# DynoHub.net
KiCad netlist of a schematic drawn in EAGLE
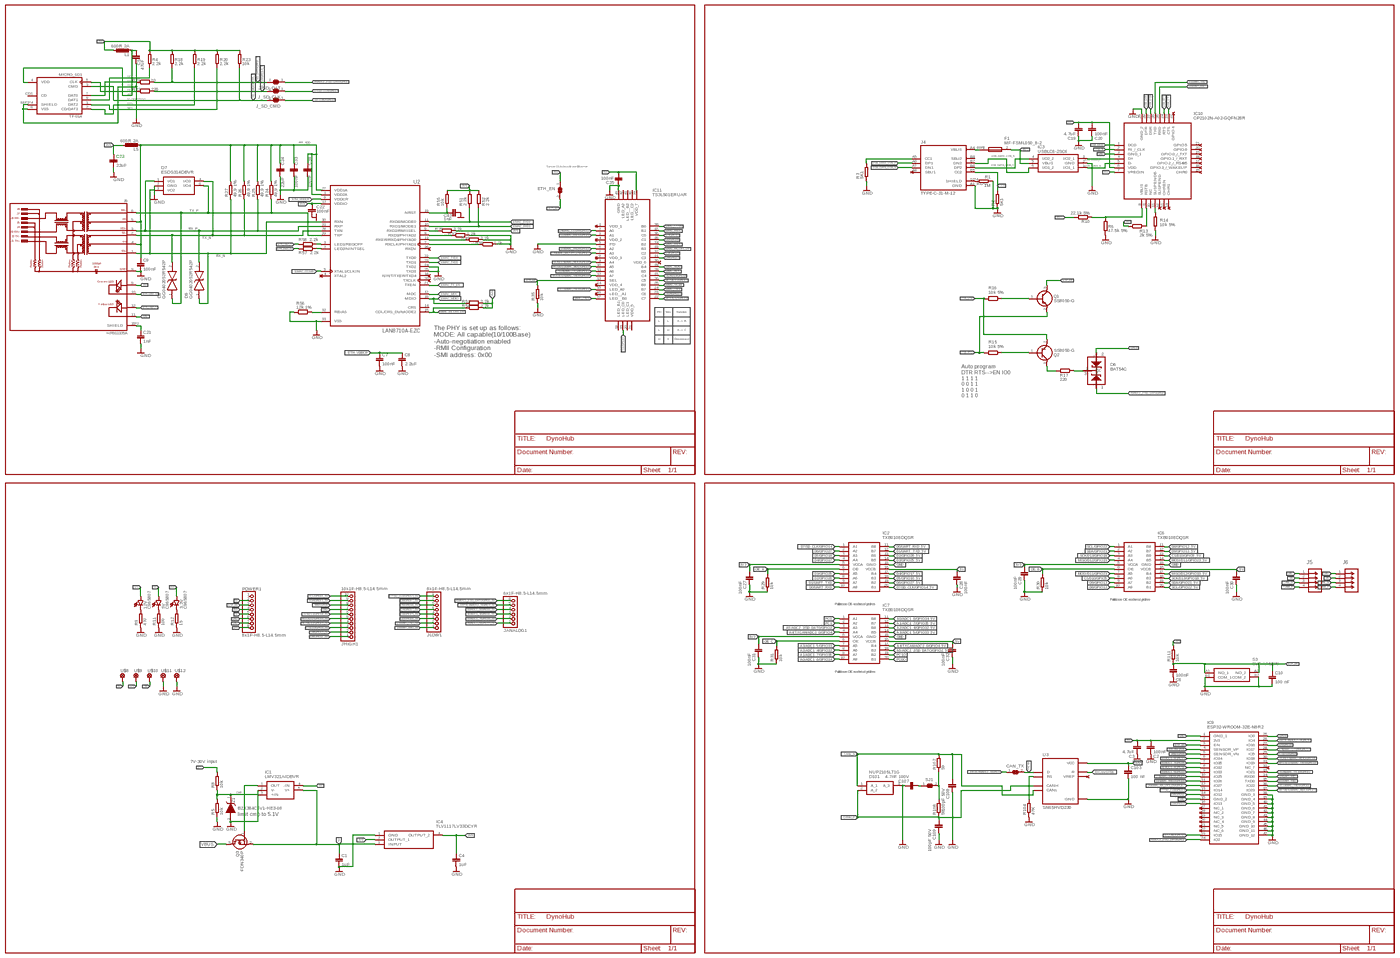
[diagram p0: schematic, sheet 1, overview]
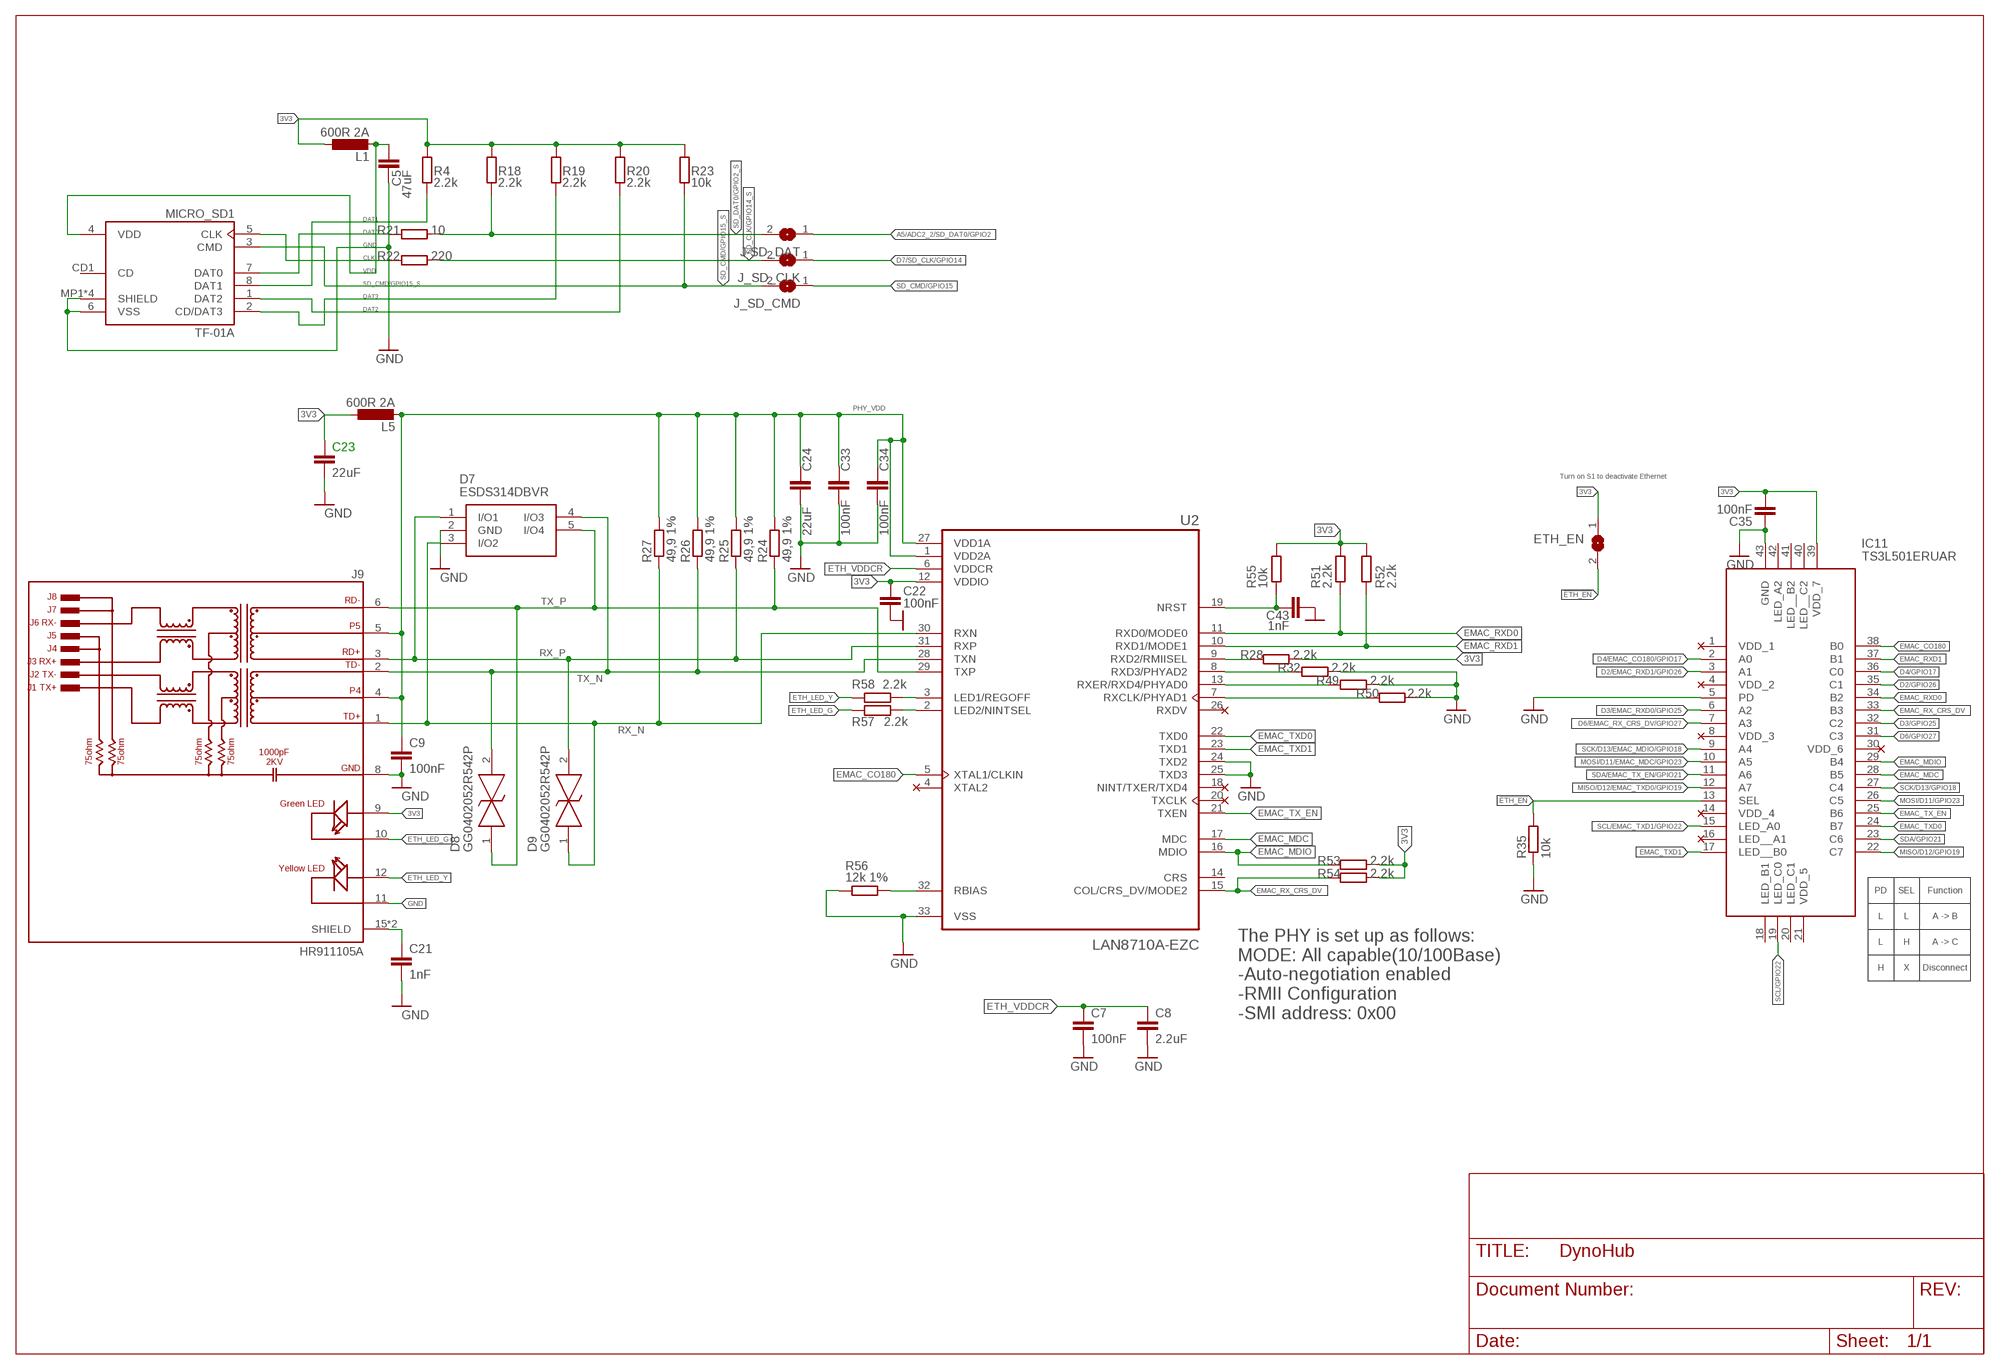
[diagram p1: schematic, sheet 1, part 1 of 4]
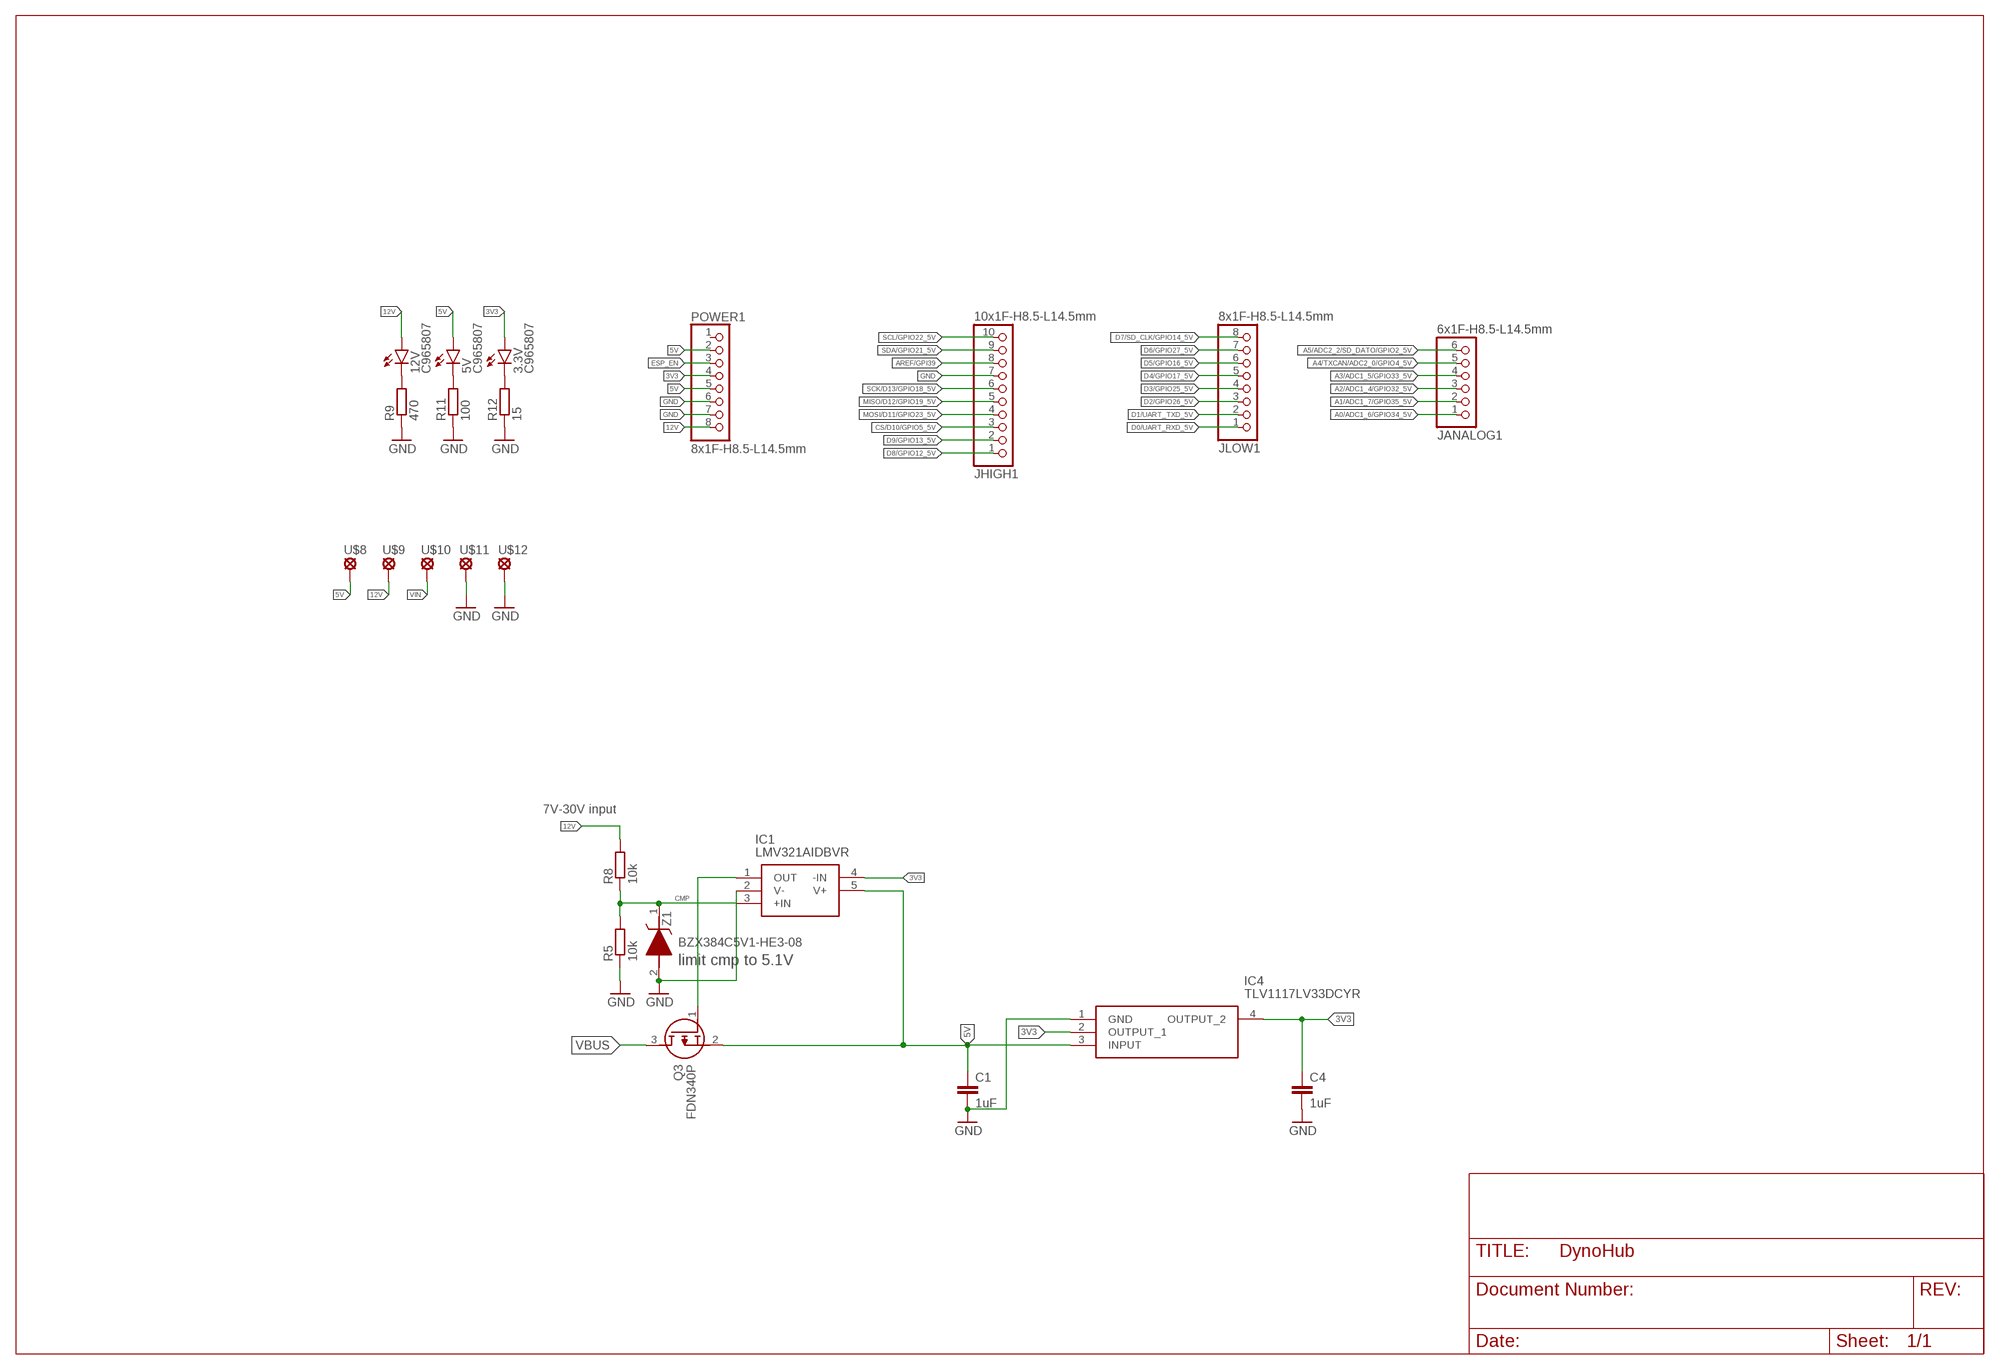
[diagram p2: schematic, sheet 1, part 2 of 4]
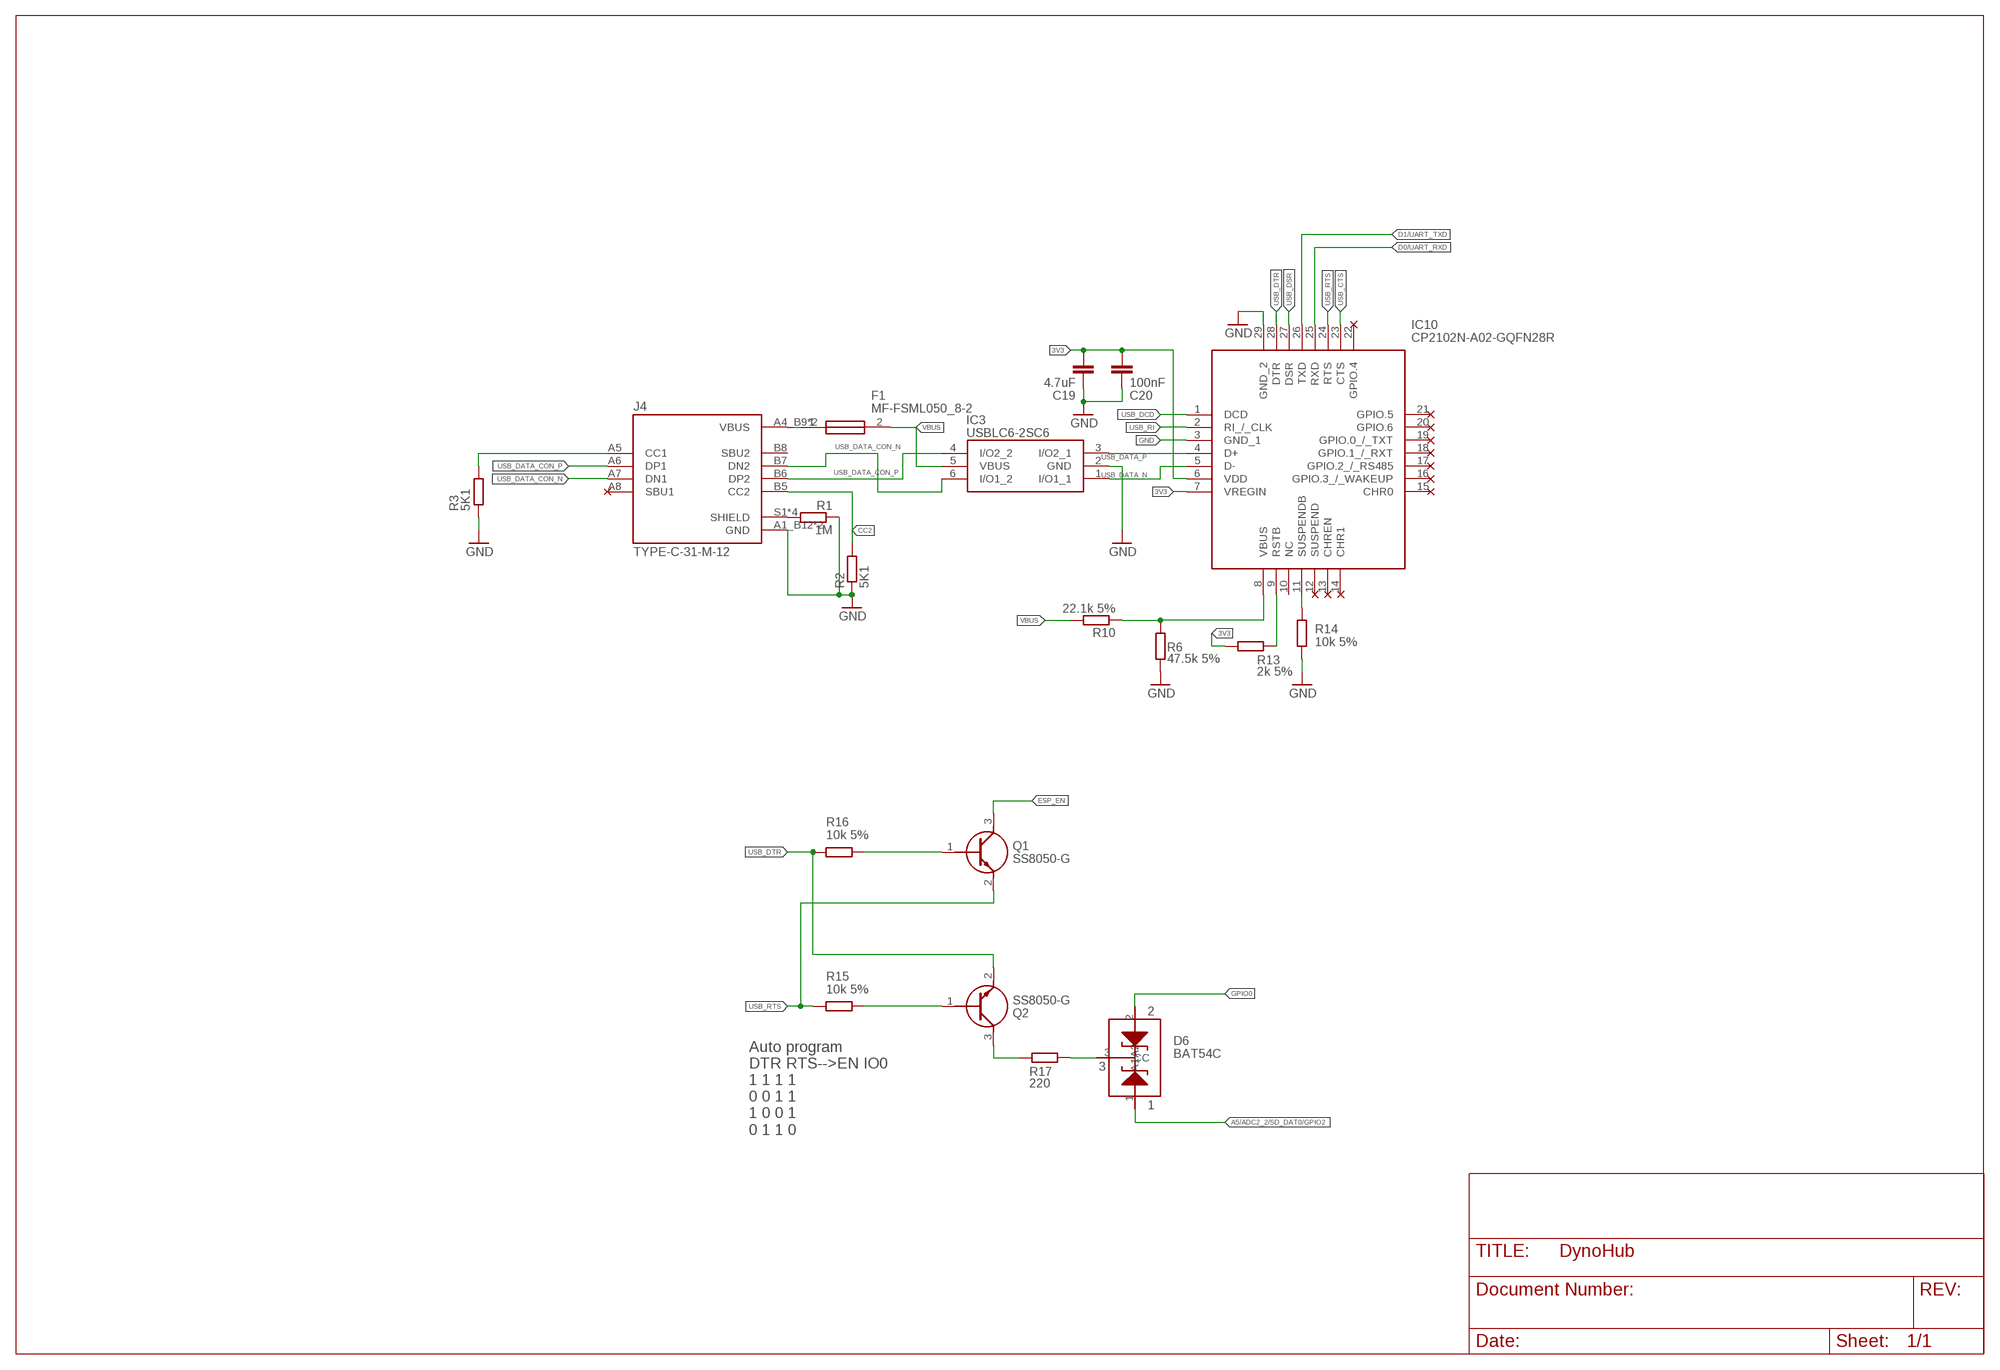
[diagram p3: schematic, sheet 1, part 3 of 4]
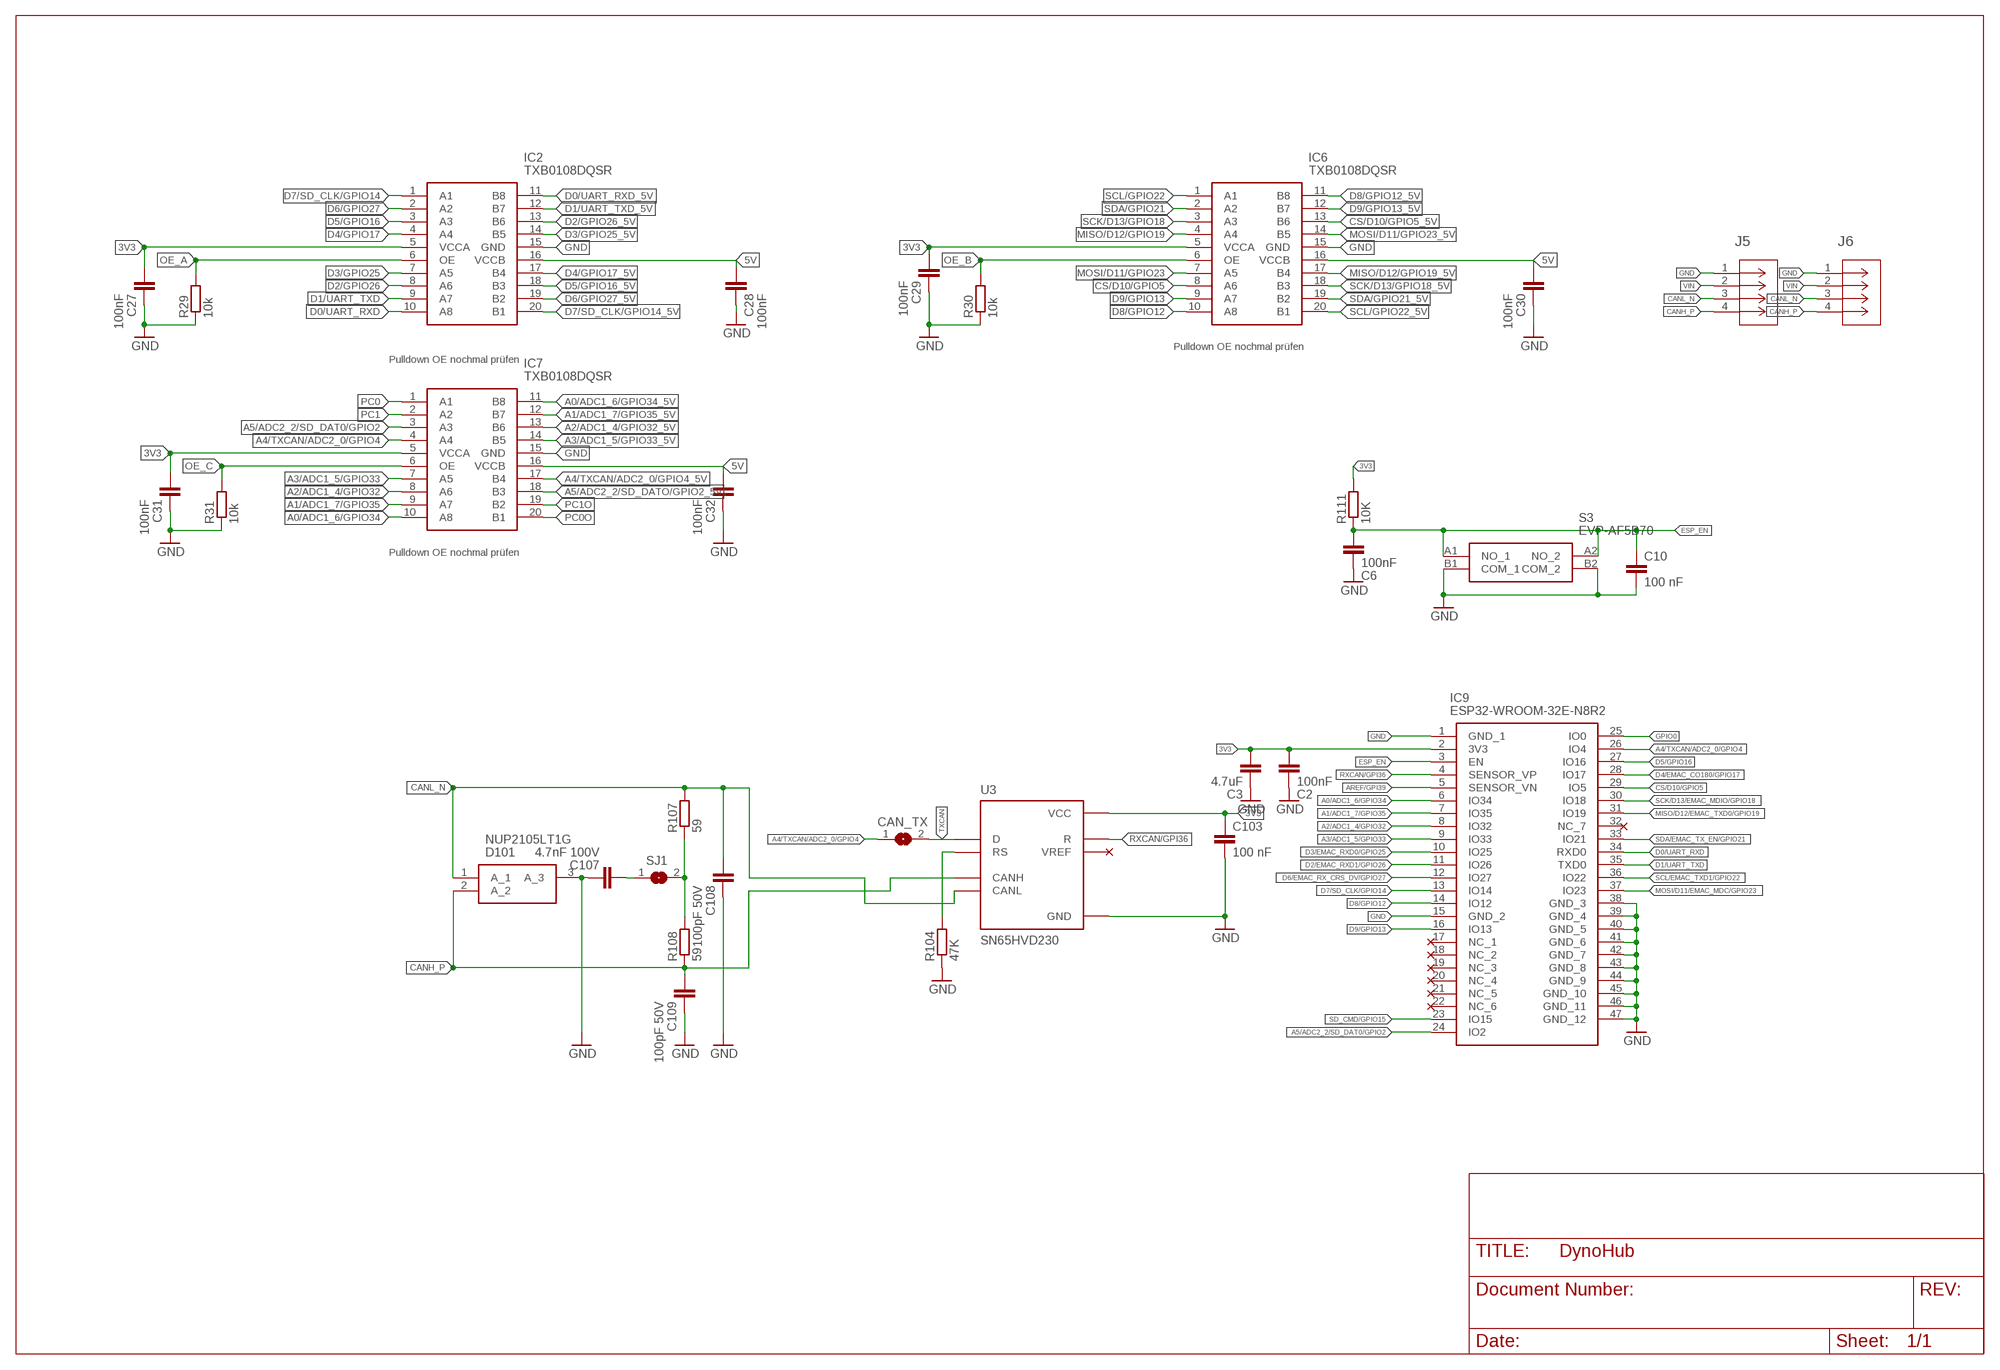
[diagram p4: schematic, sheet 1, part 4 of 4]

(export (version "E")
  (design (tool "Eeschema 10.0.6"))
  (components
    (comp (ref "3.3V")
      (value "C965807")
      (footprint "eagle-import:CHIPLED_0603")
      (libsource (lib "eagle-import") (part "LEDCHIPLED_0603"))
    )
    (comp (ref "5V")
      (value "C965807")
      (footprint "eagle-import:CHIPLED_0603")
      (libsource (lib "eagle-import") (part "LEDCHIPLED_0603"))
    )
    (comp (ref "12V")
      (value "C965807")
      (footprint "eagle-import:CHIPLED_0603")
      (libsource (lib "eagle-import") (part "LEDCHIPLED_0603"))
    )
    (comp (ref "C1")
      (value "1uF")
      (footprint "eagle-import:C0603")
      (libsource (lib "eagle-import") (part "C-EUC0603"))
    )
    (comp (ref "C2")
      (value "100nF")
      (footprint "eagle-import:C0402K")
      (libsource (lib "eagle-import") (part "C-EUC0402K"))
    )
    (comp (ref "C3")
      (value "4.7uF")
      (footprint "eagle-import:C0402K")
      (libsource (lib "eagle-import") (part "C-EUC0402K"))
    )
    (comp (ref "C4")
      (value "1uF")
      (footprint "eagle-import:C0603")
      (libsource (lib "eagle-import") (part "C-EUC0603"))
    )
    (comp (ref "C5")
      (value "47uF")
      (footprint "eagle-import:C0805")
      (libsource (lib "eagle-import") (part "C-EUC0805"))
    )
    (comp (ref "C6")
      (value "100nF")
      (footprint "eagle-import:C0402K")
      (libsource (lib "eagle-import") (part "C-EUC0402K"))
    )
    (comp (ref "C7")
      (value "100nF")
      (footprint "eagle-import:C0402K")
      (libsource (lib "eagle-import") (part "C-EUC0402K"))
    )
    (comp (ref "C8")
      (value "2.2uF")
      (footprint "eagle-import:C0402K")
      (libsource (lib "eagle-import") (part "C-EUC0402K"))
    )
    (comp (ref "C9")
      (value "100nF")
      (footprint "eagle-import:C0402K")
      (libsource (lib "eagle-import") (part "C-EUC0402K"))
    )
    (comp (ref "C10")
      (value "100 nF")
      (footprint "eagle-import:C0402K")
      (libsource (lib "eagle-import") (part "resistor_348_C-EUC0402K"))
    )
    (comp (ref "C19")
      (value "4.7uF")
      (footprint "eagle-import:C0603")
      (libsource (lib "eagle-import") (part "C-EUC0603"))
    )
    (comp (ref "C20")
      (value "100nF")
      (footprint "eagle-import:C0402K")
      (libsource (lib "eagle-import") (part "C-EUC0402K"))
    )
    (comp (ref "C21")
      (value "1nF")
      (footprint "eagle-import:C0402K")
      (libsource (lib "eagle-import") (part "C-EUC0402K"))
    )
    (comp (ref "C22")
      (value "100nF")
      (footprint "eagle-import:C0402K")
      (libsource (lib "eagle-import") (part "C-EUC0402K"))
    )
    (comp (ref "C23")
      (value "22uF")
      (footprint "eagle-import:C0603")
      (libsource (lib "eagle-import") (part "C-EUC0603"))
    )
    (comp (ref "C24")
      (value "22uF")
      (footprint "eagle-import:C0603")
      (libsource (lib "eagle-import") (part "C-EUC0603"))
    )
    (comp (ref "C27")
      (value "100nF")
      (footprint "eagle-import:C0603")
      (libsource (lib "eagle-import") (part "resistor_348_C-EUC0603"))
    )
    (comp (ref "C28")
      (value "100nF")
      (footprint "eagle-import:C0603")
      (libsource (lib "eagle-import") (part "resistor_348_C-EUC0603"))
    )
    (comp (ref "C29")
      (value "100nF")
      (footprint "eagle-import:C0402K")
      (libsource (lib "eagle-import") (part "resistor_348_C-EUC0402K"))
    )
    (comp (ref "C30")
      (value "100nF")
      (footprint "eagle-import:C0402K")
      (libsource (lib "eagle-import") (part "resistor_348_C-EUC0402K"))
    )
    (comp (ref "C31")
      (value "100nF")
      (footprint "eagle-import:C0603")
      (libsource (lib "eagle-import") (part "resistor_348_C-EUC0603"))
    )
    (comp (ref "C32")
      (value "100nF")
      (footprint "eagle-import:C0603")
      (libsource (lib "eagle-import") (part "resistor_348_C-EUC0603"))
    )
    (comp (ref "C33")
      (value "100nF")
      (footprint "eagle-import:C0402K")
      (libsource (lib "eagle-import") (part "C-EUC0402K"))
    )
    (comp (ref "C34")
      (value "100nF")
      (footprint "eagle-import:C0402K")
      (libsource (lib "eagle-import") (part "C-EUC0402K"))
    )
    (comp (ref "C35")
      (value "100nF")
      (footprint "eagle-import:C0402K")
      (libsource (lib "eagle-import") (part "C-EUC0402K"))
    )
    (comp (ref "C43")
      (value "1nF")
      (footprint "eagle-import:C0402K")
      (libsource (lib "eagle-import") (part "C-EUC0402K"))
    )
    (comp (ref "C103")
      (value "100 nF")
      (footprint "eagle-import:C0402K")
      (libsource (lib "eagle-import") (part "resistor_348_C-EUC0402K"))
    )
    (comp (ref "C107")
      (value "4.7nF 100V")
      (footprint "eagle-import:C0603")
      (libsource (lib "eagle-import") (part "resistor_348_C-EUC0603"))
    )
    (comp (ref "C108")
      (value "100pF 50V")
      (footprint "eagle-import:C0603")
      (libsource (lib "eagle-import") (part "resistor_348_C-EUC0603"))
    )
    (comp (ref "C109")
      (value "100pF 50V")
      (footprint "eagle-import:C0603")
      (libsource (lib "eagle-import") (part "resistor_348_C-EUC0603"))
    )
    (comp (ref "CAN_TX")
      (value "SJ")
      (footprint "eagle-import:SJ")
      (libsource (lib "eagle-import") (part "jumper_45683683_SJ"))
    )
    (comp (ref "D6")
      (value "BAT54C")
      (footprint "eagle-import:SOT95P240X120-3N")
      (fields (field (name "MOUSER_PART_NUMBER") "583-BAT54C"))
      (libsource (lib "eagle-import") (part "BAT54C"))
    )
    (comp (ref "D7")
      (value "ESDS314DBVR")
      (footprint "eagle-import:SOT95P280X145-5N")
      (fields (field (name "MOUSER_PART_NUMBER") "595-ESDS314DBVR"))
      (libsource (lib "eagle-import") (part "ESDS314DBVR"))
    )
    (comp (ref "D8")
      (value "GG0402052R542P")
      (footprint "eagle-import:DIONC1006X55N")
      (fields (field (name "MOUSER_PART_NUMBER") "581-GG0402052R542P"))
      (libsource (lib "eagle-import") (part "GG0402052R542P"))
    )
    (comp (ref "D9")
      (value "GG0402052R542P")
      (footprint "eagle-import:DIONC1006X55N")
      (fields (field (name "MOUSER_PART_NUMBER") "581-GG0402052R542P"))
      (libsource (lib "eagle-import") (part "GG0402052R542P"))
    )
    (comp (ref "D101")
      (value "NUP2105LT1G")
      (footprint "eagle-import:SOT96P237X111-3N")
      (fields (field (name "MOUSER_PART_NUMBER") "863-NUP2105LT1G"))
      (libsource (lib "eagle-import") (part "NUP2105LT1G"))
    )
    (comp (ref "ETH_EN")
      (value "SJ")
      (footprint "eagle-import:SJ")
      (libsource (lib "eagle-import") (part "SJ"))
    )
    (comp (ref "F1")
      (value "MF-FSML050_8-2")
      (footprint "eagle-import:FUSC1608X70N")
      (fields
        (field (name "MANUFACTURER_PART_NUMBER") "MF-FSML050/8-2")
        (field (name "MOUSER_PART_NUMBER") "652-MF-FSML050/8-2")
      )
      (libsource (lib "eagle-import") (part "MF-FSML050_8-2"))
    )
    (comp (ref "IC1")
      (value "LMV321AIDBVR")
      (footprint "eagle-import:SOT95P280X145-5N")
      (fields (field (name "MOUSER_PART_NUMBER") "595-LMV321AIDBVR"))
      (libsource (lib "eagle-import") (part "LMV321AIDBVR"))
    )
    (comp (ref "IC2")
      (value "TXB0108DQSR")
      (footprint "eagle-import:TXB0108DQSR")
      (fields (field (name "MOUSER_PART_NUMBER") "595-TXB0108DQSR"))
      (libsource (lib "eagle-import") (part "TXB0108DQSR"))
    )
    (comp (ref "IC3")
      (value "USBLC6-2SC6")
      (footprint "eagle-import:SOT95P280X145-6N")
      (fields (field (name "MOUSER_PART_NUMBER") "511-USBLC6-2SC6"))
      (libsource (lib "eagle-import") (part "USBLC6-2SC6"))
    )
    (comp (ref "IC4")
      (value "TLV1117LV33DCYR")
      (footprint "eagle-import:SOT230P700X180-4N")
      (fields (field (name "MOUSER_PART_NUMBER") "595-TLV1117LV33DCYR"))
      (libsource (lib "eagle-import") (part "TLV1117LV33DCYR"))
    )
    (comp (ref "IC6")
      (value "TXB0108DQSR")
      (footprint "eagle-import:TXB0108DQSR")
      (fields (field (name "MOUSER_PART_NUMBER") "595-TXB0108DQSR"))
      (libsource (lib "eagle-import") (part "TXB0108DQSR"))
    )
    (comp (ref "IC7")
      (value "TXB0108DQSR")
      (footprint "eagle-import:TXB0108DQSR")
      (fields (field (name "MOUSER_PART_NUMBER") "595-TXB0108DQSR"))
      (libsource (lib "eagle-import") (part "TXB0108DQSR"))
    )
    (comp (ref "IC9")
      (value "ESP32-WROOM-32E-N8R2")
      (footprint "eagle-import:ESP32WROOM32EN8R2")
      (fields (field (name "MOUSER_PART_NUMBER") "356-ESP32WRM32EN8R2"))
      (libsource (lib "eagle-import") (part "ESP32-WROOM-32E-N8R2"))
    )
    (comp (ref "IC10")
      (value "CP2102N-A02-GQFN28R")
      (footprint "eagle-import:QFN50P500X500X80-29N")
      (fields (field (name "MOUSER_PART_NUMBER") "634-CP2102NA02QFN28R"))
      (libsource (lib "eagle-import") (part "CP2102N-A02-GQFN28R"))
    )
    (comp (ref "IC11")
      (value "TS3L501ERUAR")
      (footprint "eagle-import:QFN50P350X900X80-43N")
      (fields (field (name "MOUSER_PART_NUMBER") "595-TS3L501ERUAR"))
      (libsource (lib "eagle-import") (part "TS3L501ERUAR"))
    )
    (comp (ref "J-SD_DAT")
      (value "SJ")
      (footprint "eagle-import:SJ")
      (libsource (lib "eagle-import") (part "SJ"))
    )
    (comp (ref "J4")
      (value "TYPE-C-31-M-12")
      (footprint "eagle-import:HRO_TYPE-C-31-M-12")
      (fields (field (name "MF") "HRO Electronics Co., Ltd."))
      (libsource (lib "eagle-import") (part "TYPE-C-31-M-12"))
    )
    (comp (ref "J5")
      (value "1718570004CONN_SD-171857-0001_M265_04_MO")
      (footprint "eagle-import:CONN_SD-171857-0001_M265_04_MO")
      (fields
        (field (name "MANUFACTURER_PART_NUMBER") "1718570004")
        (field (name "COPYRIGHT") "Copyright (C) 2025 Ultra Librarian. All rights reserved.")
      )
      (libsource (lib "eagle-import") (part "1718570004CONN_SD-171857-0001_M265_04_MO"))
    )
    (comp (ref "J6")
      (value "1718570004CONN_SD-171857-0001_M265_04_MO")
      (footprint "eagle-import:CONN_SD-171857-0001_M265_04_MO")
      (fields
        (field (name "MANUFACTURER_PART_NUMBER") "1718570004")
        (field (name "COPYRIGHT") "Copyright (C) 2025 Ultra Librarian. All rights reserved.")
      )
      (libsource (lib "eagle-import") (part "1718570004CONN_SD-171857-0001_M265_04_MO"))
    )
    (comp (ref "J9")
      (value "HR911105A")
      (footprint "eagle-import:HANRUN_HR911105A")
      (fields (field (name "MF") "hanrun"))
      (libsource (lib "eagle-import") (part "HR911105A"))
    )
    (comp (ref "JANALOG1")
      (value "6x1F-H8.5-L14.5mm")
      (footprint "eagle-import:1X06")
      (libsource (lib "eagle-import") (part "PINHD-1X6"))
    )
    (comp (ref "JHIGH1")
      (value "10x1F-H8.5-L14.5mm")
      (footprint "eagle-import:1X10")
      (libsource (lib "eagle-import") (part "PINHD-1X10"))
    )
    (comp (ref "JLOW1")
      (value "8x1F-H8.5-L14.5mm")
      (footprint "eagle-import:1X08")
      (libsource (lib "eagle-import") (part "PINHD-1X8"))
    )
    (comp (ref "J_SD_CLK")
      (value "SJ")
      (footprint "eagle-import:SJ")
      (libsource (lib "eagle-import") (part "SJ"))
    )
    (comp (ref "J_SD_CMD")
      (value "SJ")
      (footprint "eagle-import:SJ")
      (libsource (lib "eagle-import") (part "SJ"))
    )
    (comp (ref "L1")
      (value "600R 2A")
      (footprint "eagle-import:L2012C")
      (libsource (lib "eagle-import") (part "L-EUL2012C"))
    )
    (comp (ref "L5")
      (value "600R 2A")
      (footprint "eagle-import:L2012C")
      (libsource (lib "eagle-import") (part "L-EUL2012C"))
    )
    (comp (ref "MICRO_SD1")
      (value "TF-01A")
      (footprint "eagle-import:TF-01A")
      (fields (field (name "MF") "HRO Electronics Co., Ltd."))
      (libsource (lib "eagle-import") (part "TF-01A"))
    )
    (comp (ref "POWER1")
      (value "8x1F-H8.5-L14.5mm")
      (footprint "eagle-import:1X08")
      (libsource (lib "eagle-import") (part "PINHD-1X8"))
    )
    (comp (ref "Q1")
      (value "SS8050-G")
      (footprint "eagle-import:SOT95P240X115-3N")
      (fields (field (name "MOUSER_PART_NUMBER") "750-SS8050-G"))
      (libsource (lib "eagle-import") (part "SS8050-G"))
    )
    (comp (ref "Q2")
      (value "SS8050-G")
      (footprint "eagle-import:SOT95P240X115-3N")
      (fields (field (name "MOUSER_PART_NUMBER") "750-SS8050-G"))
      (libsource (lib "eagle-import") (part "SS8050-G"))
    )
    (comp (ref "Q3")
      (value "FDN340P")
      (footprint "eagle-import:SOT95P237X112-3N")
      (fields (field (name "MOUSER_PART_NUMBER") "512-FDN340P"))
      (libsource (lib "eagle-import") (part "FDN340P"))
    )
    (comp (ref "R1")
      (value "1M")
      (footprint "eagle-import:R0603")
      (libsource (lib "eagle-import") (part "resistor_348_R-EU_R0603"))
    )
    (comp (ref "R2")
      (value "5K1")
      (footprint "eagle-import:R0603")
      (libsource (lib "eagle-import") (part "resistor_348_R-EU_R0603"))
    )
    (comp (ref "R3")
      (value "5K1")
      (footprint "eagle-import:R0603")
      (libsource (lib "eagle-import") (part "resistor_348_R-EU_R0603"))
    )
    (comp (ref "R4")
      (value "2.2k")
      (footprint "eagle-import:R0402")
      (libsource (lib "eagle-import") (part "R-EU_R0402"))
    )
    (comp (ref "R5")
      (value "10k")
      (footprint "eagle-import:R0603")
      (libsource (lib "eagle-import") (part "resistor_348_R-EU_R0603"))
    )
    (comp (ref "R6")
      (value "47.5k 5%")
      (footprint "eagle-import:R0402")
      (libsource (lib "eagle-import") (part "R-EU_R0402"))
    )
    (comp (ref "R8")
      (value "10k")
      (footprint "eagle-import:R0603")
      (libsource (lib "eagle-import") (part "resistor_348_R-EU_R0603"))
    )
    (comp (ref "R9")
      (value "470")
      (footprint "eagle-import:R0603")
      (libsource (lib "eagle-import") (part "resistor_348_R-EU_R0603"))
    )
    (comp (ref "R10")
      (value "22.1k 5%")
      (footprint "eagle-import:R0402")
      (libsource (lib "eagle-import") (part "R-EU_R0402"))
    )
    (comp (ref "R11")
      (value "100")
      (footprint "eagle-import:R0603")
      (libsource (lib "eagle-import") (part "resistor_348_R-EU_R0603"))
    )
    (comp (ref "R12")
      (value "15")
      (footprint "eagle-import:R0603")
      (libsource (lib "eagle-import") (part "resistor_348_R-EU_R0603"))
    )
    (comp (ref "R13")
      (value "2k 5%")
      (footprint "eagle-import:R0402")
      (libsource (lib "eagle-import") (part "R-EU_R0402"))
    )
    (comp (ref "R14")
      (value "10k 5%")
      (footprint "eagle-import:R0402")
      (libsource (lib "eagle-import") (part "R-EU_R0402"))
    )
    (comp (ref "R15")
      (value "10k 5%")
      (footprint "eagle-import:R0402")
      (libsource (lib "eagle-import") (part "R-EU_R0402"))
    )
    (comp (ref "R16")
      (value "10k 5%")
      (footprint "eagle-import:R0402")
      (libsource (lib "eagle-import") (part "R-EU_R0402"))
    )
    (comp (ref "R17")
      (value "220")
      (footprint "eagle-import:R0402")
      (libsource (lib "eagle-import") (part "R-EU_R0402"))
    )
    (comp (ref "R18")
      (value "2.2k")
      (footprint "eagle-import:R0402")
      (libsource (lib "eagle-import") (part "R-EU_R0402"))
    )
    (comp (ref "R19")
      (value "2.2k")
      (footprint "eagle-import:R0402")
      (libsource (lib "eagle-import") (part "R-EU_R0402"))
    )
    (comp (ref "R20")
      (value "2.2k")
      (footprint "eagle-import:R0402")
      (libsource (lib "eagle-import") (part "R-EU_R0402"))
    )
    (comp (ref "R21")
      (value "10")
      (footprint "eagle-import:R0402")
      (libsource (lib "eagle-import") (part "R-EU_R0402"))
    )
    (comp (ref "R22")
      (value "220")
      (footprint "eagle-import:R0402")
      (libsource (lib "eagle-import") (part "R-EU_R0402"))
    )
    (comp (ref "R23")
      (value "10k")
      (footprint "eagle-import:R0402")
      (libsource (lib "eagle-import") (part "R-EU_R0402"))
    )
    (comp (ref "R24")
      (value "49,9 1%")
      (footprint "eagle-import:R0402")
      (libsource (lib "eagle-import") (part "R-EU_R0402"))
    )
    (comp (ref "R25")
      (value "49,9 1%")
      (footprint "eagle-import:R0402")
      (libsource (lib "eagle-import") (part "R-EU_R0402"))
    )
    (comp (ref "R26")
      (value "49,9 1%")
      (footprint "eagle-import:R0402")
      (libsource (lib "eagle-import") (part "R-EU_R0402"))
    )
    (comp (ref "R27")
      (value "49,9 1%")
      (footprint "eagle-import:R0402")
      (libsource (lib "eagle-import") (part "R-EU_R0402"))
    )
    (comp (ref "R28")
      (value "2.2k")
      (footprint "eagle-import:R0402")
      (libsource (lib "eagle-import") (part "R-EU_R0402"))
    )
    (comp (ref "R29")
      (value "10k")
      (footprint "eagle-import:R0603")
      (libsource (lib "eagle-import") (part "resistor_348_R-EU_R0603"))
    )
    (comp (ref "R30")
      (value "10k")
      (footprint "eagle-import:R0402")
      (libsource (lib "eagle-import") (part "resistor_348_R-EU_R0402"))
    )
    (comp (ref "R31")
      (value "10k")
      (footprint "eagle-import:R0603")
      (libsource (lib "eagle-import") (part "resistor_348_R-EU_R0603"))
    )
    (comp (ref "R32")
      (value "2.2k")
      (footprint "eagle-import:R0402")
      (libsource (lib "eagle-import") (part "R-EU_R0402"))
    )
    (comp (ref "R35")
      (value "10k")
      (footprint "eagle-import:R0603")
      (libsource (lib "eagle-import") (part "resistor_348_R-EU_R0603"))
    )
    (comp (ref "R49")
      (value "2.2k")
      (footprint "eagle-import:R0402")
      (libsource (lib "eagle-import") (part "R-EU_R0402"))
    )
    (comp (ref "R50")
      (value "2.2k")
      (footprint "eagle-import:R0402")
      (libsource (lib "eagle-import") (part "R-EU_R0402"))
    )
    (comp (ref "R51")
      (value "2.2k")
      (footprint "eagle-import:R0402")
      (libsource (lib "eagle-import") (part "R-EU_R0402"))
    )
    (comp (ref "R52")
      (value "2.2k")
      (footprint "eagle-import:R0402")
      (libsource (lib "eagle-import") (part "R-EU_R0402"))
    )
    (comp (ref "R53")
      (value "2.2k")
      (footprint "eagle-import:R0603")
      (libsource (lib "eagle-import") (part "R-EU_R0603"))
    )
    (comp (ref "R54")
      (value "2.2k")
      (footprint "eagle-import:R0603")
      (libsource (lib "eagle-import") (part "R-EU_R0603"))
    )
    (comp (ref "R55")
      (value "10k")
      (footprint "eagle-import:R0402")
      (libsource (lib "eagle-import") (part "R-EU_R0402"))
    )
    (comp (ref "R56")
      (value "12k 1%")
      (footprint "eagle-import:R0402")
      (libsource (lib "eagle-import") (part "R-EU_R0402"))
    )
    (comp (ref "R57")
      (value "2.2k")
      (footprint "eagle-import:R0402")
      (libsource (lib "eagle-import") (part "R-EU_R0402"))
    )
    (comp (ref "R58")
      (value "2.2k")
      (footprint "eagle-import:R0402")
      (libsource (lib "eagle-import") (part "R-EU_R0402"))
    )
    (comp (ref "R104")
      (value "47K")
      (footprint "eagle-import:R0603")
      (libsource (lib "eagle-import") (part "resistor_348_R-EU_R0603"))
    )
    (comp (ref "R107")
      (value "59")
      (footprint "eagle-import:R0603")
      (libsource (lib "eagle-import") (part "resistor_348_R-EU_R0603"))
    )
    (comp (ref "R108")
      (value "59")
      (footprint "eagle-import:R0603")
      (libsource (lib "eagle-import") (part "resistor_348_R-EU_R0603"))
    )
    (comp (ref "R111")
      (value "10K")
      (footprint "eagle-import:R0402")
      (libsource (lib "eagle-import") (part "R-EU_R0402"))
    )
    (comp (ref "S3")
      (value "EVP-AF5B70")
      (footprint "eagle-import:EVPAF5B70")
      (fields (field (name "MOUSER_PART_NUMBER") "667-EVP-AF5B70"))
      (libsource (lib "eagle-import") (part "EVP-AF5B70"))
    )
    (comp (ref "SJ1")
      (value "SJ")
      (footprint "eagle-import:SJ")
      (libsource (lib "eagle-import") (part "jumper_45683683_SJ"))
    )
    (comp (ref "U$1") (value "NC") (footprint "eagle-import:NC") (libsource (lib "eagle-import") (part "NC")))
    (comp (ref "U$2") (value "NC") (footprint "eagle-import:NC") (libsource (lib "eagle-import") (part "NC")))
    (comp (ref "U$3") (value "NC") (footprint "eagle-import:NC") (libsource (lib "eagle-import") (part "NC")))
    (comp (ref "U$4") (value "NC") (footprint "eagle-import:NC") (libsource (lib "eagle-import") (part "NC")))
    (comp (ref "U$5") (value "NC") (footprint "eagle-import:NC") (libsource (lib "eagle-import") (part "NC")))
    (comp (ref "U$6") (value "NC") (footprint "eagle-import:NC") (libsource (lib "eagle-import") (part "NC")))
    (comp (ref "U$7") (value "NC") (footprint "eagle-import:NC") (libsource (lib "eagle-import") (part "NC")))
    (comp (ref "U$8")
      (value "2X3MM_PAD")
      (footprint "eagle-import:2X3MM_PAD")
      (libsource (lib "eagle-import") (part "2X3MM_PAD"))
    )
    (comp (ref "U$9")
      (value "2X3MM_PAD")
      (footprint "eagle-import:2X3MM_PAD")
      (libsource (lib "eagle-import") (part "2X3MM_PAD"))
    )
    (comp (ref "U$10")
      (value "2X3MM_PAD")
      (footprint "eagle-import:2X3MM_PAD")
      (libsource (lib "eagle-import") (part "2X3MM_PAD"))
    )
    (comp (ref "U$11")
      (value "2X3MM_PAD")
      (footprint "eagle-import:2X3MM_PAD")
      (libsource (lib "eagle-import") (part "2X3MM_PAD"))
    )
    (comp (ref "U$12")
      (value "2X3MM_PAD")
      (footprint "eagle-import:2X3MM_PAD")
      (libsource (lib "eagle-import") (part "2X3MM_PAD"))
    )
    (comp (ref "U$13")
      (value "NC")
      (footprint "eagle-import:NC")
      (libsource (lib "eagle-import") (part "NC"))
    )
    (comp (ref "U$14")
      (value "NC")
      (footprint "eagle-import:NC")
      (libsource (lib "eagle-import") (part "NC"))
    )
    (comp (ref "U$15")
      (value "NC")
      (footprint "eagle-import:NC")
      (libsource (lib "eagle-import") (part "NC"))
    )
    (comp (ref "U$16")
      (value "NC")
      (footprint "eagle-import:NC")
      (libsource (lib "eagle-import") (part "NC"))
    )
    (comp (ref "U$17")
      (value "NC")
      (footprint "eagle-import:NC")
      (libsource (lib "eagle-import") (part "NC"))
    )
    (comp (ref "U$18")
      (value "NC")
      (footprint "eagle-import:NC")
      (libsource (lib "eagle-import") (part "NC"))
    )
    (comp (ref "U$19")
      (value "NC")
      (footprint "eagle-import:NC")
      (libsource (lib "eagle-import") (part "NC"))
    )
    (comp (ref "U$20")
      (value "NC")
      (footprint "eagle-import:NC")
      (libsource (lib "eagle-import") (part "NC"))
    )
    (comp (ref "U$21")
      (value "NC")
      (footprint "eagle-import:NC")
      (libsource (lib "eagle-import") (part "NC"))
    )
    (comp (ref "U$22")
      (value "NC")
      (footprint "eagle-import:NC")
      (libsource (lib "eagle-import") (part "NC"))
    )
    (comp (ref "U$23")
      (value "NC")
      (footprint "eagle-import:NC")
      (libsource (lib "eagle-import") (part "NC"))
    )
    (comp (ref "U$24")
      (value "NC")
      (footprint "eagle-import:NC")
      (libsource (lib "eagle-import") (part "NC"))
    )
    (comp (ref "U$25")
      (value "NC")
      (footprint "eagle-import:NC")
      (libsource (lib "eagle-import") (part "NC"))
    )
    (comp (ref "U$26")
      (value "NC")
      (footprint "eagle-import:NC")
      (libsource (lib "eagle-import") (part "NC"))
    )
    (comp (ref "U$27")
      (value "NC")
      (footprint "eagle-import:NC")
      (libsource (lib "eagle-import") (part "NC"))
    )
    (comp (ref "U$28")
      (value "NC")
      (footprint "eagle-import:NC")
      (libsource (lib "eagle-import") (part "NC"))
    )
    (comp (ref "U$29")
      (value "NC")
      (footprint "eagle-import:NC")
      (libsource (lib "eagle-import") (part "NC"))
    )
    (comp (ref "U$30")
      (value "NC")
      (footprint "eagle-import:NC")
      (libsource (lib "eagle-import") (part "NC"))
    )
    (comp (ref "U$31")
      (value "NC")
      (footprint "eagle-import:NC")
      (libsource (lib "eagle-import") (part "NC"))
    )
    (comp (ref "U$32")
      (value "NC")
      (footprint "eagle-import:NC")
      (libsource (lib "eagle-import") (part "NC"))
    )
    (comp (ref "U$33")
      (value "NC")
      (footprint "eagle-import:NC")
      (libsource (lib "eagle-import") (part "NC"))
    )
    (comp (ref "U$34")
      (value "NC")
      (footprint "eagle-import:NC")
      (libsource (lib "eagle-import") (part "NC"))
    )
    (comp (ref "U$35")
      (value "NC")
      (footprint "eagle-import:NC")
      (libsource (lib "eagle-import") (part "NC"))
    )
    (comp (ref "U2")
      (value "LAN8710A-EZC")
      (footprint "eagle-import:QFN50P500X500X100-33N")
      (fields (field (name "MF") "Microchip"))
      (libsource (lib "eagle-import") (part "LAN8710A-EZC"))
    )
    (comp (ref "U3")
      (value "SN65HVD230")
      (footprint "eagle-import:SOIC127P599X175-8N")
      (fields (field (name "MF") "Texas Instruments"))
      (libsource (lib "eagle-import") (part "SN65HVD230"))
    )
    (comp (ref "Z1")
      (value "BZX384C5V1-HE3-08")
      (footprint "eagle-import:SOD2713X115N")
      (fields (field (name "MOUSER_PART_NUMBER") "78-BZX384C5V1-HE3-08"))
      (libsource (lib "eagle-import") (part "BZX384C5V1-HE3-08"))
    )
  )
  (nets
    (net (code "1") (name "/CLK") (class "Default")
      (node (ref "MICRO_SD1") (pin "5") (pinfunction "CLK_5") (pintype "bidirectional"))
      (node (ref "R22") (pin "1") (pinfunction "1_1") (pintype "passive"))
    )
    (net (code "2") (name "/CMP") (class "Default")
      (node (ref "IC1") (pin "3") (pinfunction "+IN_3") (pintype "bidirectional"))
      (node (ref "R5") (pin "2") (pinfunction "2_2") (pintype "passive"))
      (node (ref "R8") (pin "1") (pinfunction "1_1") (pintype "passive"))
      (node (ref "Z1") (pin "1") (pinfunction "K_1") (pintype "bidirectional"))
    )
    (net (code "3") (name "/DAT0") (class "Default")
      (node (ref "MICRO_SD1") (pin "7") (pinfunction "DAT0_7") (pintype "bidirectional"))
      (node (ref "R21") (pin "1") (pinfunction "1_1") (pintype "passive"))
    )
    (net (code "4") (name "/DAT1") (class "Default")
      (node (ref "MICRO_SD1") (pin "8") (pinfunction "DAT1_8") (pintype "bidirectional"))
      (node (ref "R4") (pin "1") (pinfunction "1_1") (pintype "passive"))
    )
    (net (code "5") (name "/DAT2") (class "Default")
      (node (ref "MICRO_SD1") (pin "1") (pinfunction "DAT2_1") (pintype "bidirectional"))
      (node (ref "R20") (pin "1") (pinfunction "1_1") (pintype "passive"))
    )
    (net (code "6") (name "/DAT3") (class "Default")
      (node (ref "MICRO_SD1") (pin "2") (pinfunction "CD/DAT3_2") (pintype "bidirectional"))
      (node (ref "R19") (pin "1") (pinfunction "1_1") (pintype "passive"))
    )
    (net (code "7") (name "/PHY_VDD") (class "Default")
      (node (ref "C24") (pin "1") (pinfunction "1_1") (pintype "passive"))
      (node (ref "C33") (pin "1") (pinfunction "1_1") (pintype "passive"))
      (node (ref "C34") (pin "1") (pinfunction "1_1") (pintype "passive"))
      (node (ref "C9") (pin "1") (pinfunction "1_1") (pintype "passive"))
      (node (ref "J9") (pin "4") (pinfunction "P4_4") (pintype "passive"))
      (node (ref "J9") (pin "5") (pinfunction "P5_5") (pintype "passive"))
      (node (ref "L5") (pin "2") (pinfunction "2_2") (pintype "passive"))
      (node (ref "R24") (pin "2") (pinfunction "2_2") (pintype "passive"))
      (node (ref "R25") (pin "2") (pinfunction "2_2") (pintype "passive"))
      (node (ref "R26") (pin "2") (pinfunction "2_2") (pintype "passive"))
      (node (ref "R27") (pin "2") (pinfunction "2_2") (pintype "passive"))
      (node (ref "U2") (pin "1") (pinfunction "VDD2A_1") (pintype "power_in"))
      (node (ref "U2") (pin "27") (pinfunction "VDD1A_27") (pintype "power_in"))
    )
    (net (code "8") (name "/RX_N") (class "Default")
      (node (ref "D7") (pin "3") (pinfunction "I/O2_3") (pintype "bidirectional"))
      (node (ref "D9") (pin "1") (pinfunction "1_1") (pintype "bidirectional"))
      (node (ref "J9") (pin "1") (pinfunction "TD+_1") (pintype "passive"))
      (node (ref "R27") (pin "1") (pinfunction "1_1") (pintype "passive"))
      (node (ref "U2") (pin "30") (pinfunction "RXN_30") (pintype "bidirectional"))
    )
    (net (code "9") (name "/RX_P") (class "Default")
      (node (ref "D7") (pin "1") (pinfunction "I/O1_1") (pintype "bidirectional"))
      (node (ref "D9") (pin "2") (pinfunction "2_2") (pintype "bidirectional"))
      (node (ref "J9") (pin "3") (pinfunction "RD+_3") (pintype "passive"))
      (node (ref "R25") (pin "1") (pinfunction "1_1") (pintype "passive"))
      (node (ref "U2") (pin "31") (pinfunction "RXP_31") (pintype "bidirectional"))
    )
    (net (code "10") (name "/TX_N") (class "Default")
      (node (ref "D7") (pin "4") (pinfunction "I/O3_4") (pintype "bidirectional"))
      (node (ref "D8") (pin "2") (pinfunction "2_2") (pintype "bidirectional"))
      (node (ref "J9") (pin "2") (pinfunction "TD-_2") (pintype "passive"))
      (node (ref "R26") (pin "1") (pinfunction "1_1") (pintype "passive"))
      (node (ref "U2") (pin "28") (pinfunction "TXN_28") (pintype "bidirectional"))
    )
    (net (code "11") (name "/TX_P") (class "Default")
      (node (ref "D7") (pin "5") (pinfunction "I/O4_5") (pintype "bidirectional"))
      (node (ref "D8") (pin "1") (pinfunction "1_1") (pintype "bidirectional"))
      (node (ref "J9") (pin "6") (pinfunction "RD-_6") (pintype "passive"))
      (node (ref "R24") (pin "1") (pinfunction "1_1") (pintype "passive"))
      (node (ref "U2") (pin "29") (pinfunction "TXP_29") (pintype "bidirectional"))
    )
    (net (code "12") (name "/USB_DATA_N") (class "Default")
      (node (ref "IC10") (pin "5") (pinfunction "D-_5") (pintype "bidirectional"))
      (node (ref "IC3") (pin "1") (pinfunction "I/O1_1_1") (pintype "bidirectional"))
    )
    (net (code "13") (name "/USB_DATA_P") (class "Default")
      (node (ref "IC10") (pin "4") (pinfunction "D+_4") (pintype "bidirectional"))
      (node (ref "IC3") (pin "3") (pinfunction "I/O2_1_3") (pintype "bidirectional"))
    )
    (net (code "14") (name "/VDD") (class "Default")
      (node (ref "C5") (pin "2") (pinfunction "2_2") (pintype "passive"))
      (node (ref "L1") (pin "2") (pinfunction "2_2") (pintype "passive"))
      (node (ref "MICRO_SD1") (pin "4") (pinfunction "VDD_4") (pintype "power_in"))
    )
    (net (code "15") (name "/~{ETH_EN}") (class "Default")
      (node (ref "ETH_EN") (pin "2") (pinfunction "2_2") (pintype "passive"))
      (node (ref "IC11") (pin "13") (pinfunction "SEL_13") (pintype "bidirectional"))
      (node (ref "R35") (pin "2") (pinfunction "2_2") (pintype "passive"))
    )
    (net (code "16") (name "3V3") (class "Default")
      (node (ref "3.3V") (pin "A") (pinfunction "A_A") (pintype "passive"))
      (node (ref "C103") (pin "1") (pinfunction "1_1") (pintype "passive"))
      (node (ref "C19") (pin "1") (pinfunction "1_1") (pintype "passive"))
      (node (ref "C2") (pin "1") (pinfunction "1_1") (pintype "passive"))
      (node (ref "C20") (pin "1") (pinfunction "1_1") (pintype "passive"))
      (node (ref "C22") (pin "1") (pinfunction "1_1") (pintype "passive"))
      (node (ref "C23") (pin "1") (pinfunction "1_1") (pintype "passive"))
      (node (ref "C27") (pin "2") (pinfunction "2_2") (pintype "passive"))
      (node (ref "C29") (pin "2") (pinfunction "2_2") (pintype "passive"))
      (node (ref "C3") (pin "1") (pinfunction "1_1") (pintype "passive"))
      (node (ref "C31") (pin "2") (pinfunction "2_2") (pintype "passive"))
      (node (ref "C35") (pin "2") (pinfunction "2_2") (pintype "passive"))
      (node (ref "C4") (pin "1") (pinfunction "1_1") (pintype "passive"))
      (node (ref "ETH_EN") (pin "1") (pinfunction "1_1") (pintype "passive"))
      (node (ref "IC1") (pin "4") (pinfunction "-IN_4") (pintype "bidirectional"))
      (node (ref "IC10") (pin "6") (pinfunction "VDD_6") (pintype "bidirectional"))
      (node (ref "IC10") (pin "7") (pinfunction "VREGIN_7") (pintype "bidirectional"))
      (node (ref "IC11") (pin "39") (pinfunction "VDD_7_39") (pintype "bidirectional"))
      (node (ref "IC2") (pin "5") (pinfunction "VCCA_5") (pintype "bidirectional"))
      (node (ref "IC4") (pin "2") (pinfunction "OUTPUT_1_2") (pintype "bidirectional"))
      (node (ref "IC4") (pin "4") (pinfunction "OUTPUT_2_4") (pintype "bidirectional"))
      (node (ref "IC6") (pin "5") (pinfunction "VCCA_5") (pintype "bidirectional"))
      (node (ref "IC7") (pin "5") (pinfunction "VCCA_5") (pintype "bidirectional"))
      (node (ref "IC9") (pin "2") (pinfunction "3V3_2") (pintype "bidirectional"))
      (node (ref "J9") (pin "9") (pinfunction "GA_9") (pintype "passive"))
      (node (ref "L1") (pin "1") (pinfunction "1_1") (pintype "passive"))
      (node (ref "L5") (pin "1") (pinfunction "1_1") (pintype "passive"))
      (node (ref "POWER1") (pin "4") (pinfunction "4_4") (pintype "passive"))
      (node (ref "R111") (pin "2") (pinfunction "2_2") (pintype "passive"))
      (node (ref "R13") (pin "1") (pinfunction "1_1") (pintype "passive"))
      (node (ref "R18") (pin "2") (pinfunction "2_2") (pintype "passive"))
      (node (ref "R19") (pin "2") (pinfunction "2_2") (pintype "passive"))
      (node (ref "R20") (pin "2") (pinfunction "2_2") (pintype "passive"))
      (node (ref "R23") (pin "2") (pinfunction "2_2") (pintype "passive"))
      (node (ref "R28") (pin "2") (pinfunction "2_2") (pintype "passive"))
      (node (ref "R4") (pin "2") (pinfunction "2_2") (pintype "passive"))
      (node (ref "R51") (pin "2") (pinfunction "2_2") (pintype "passive"))
      (node (ref "R52") (pin "2") (pinfunction "2_2") (pintype "passive"))
      (node (ref "R53") (pin "2") (pinfunction "2_2") (pintype "passive"))
      (node (ref "R54") (pin "2") (pinfunction "2_2") (pintype "passive"))
      (node (ref "R55") (pin "2") (pinfunction "2_2") (pintype "passive"))
      (node (ref "U2") (pin "12") (pinfunction "VDDIO_12") (pintype "power_in"))
      (node (ref "U3") (pin "3") (pinfunction "VCC_3") (pintype "power_in"))
    )
    (net (code "17") (name "5V") (class "Default")
      (node (ref "5V") (pin "A") (pinfunction "A_A") (pintype "passive"))
      (node (ref "C1") (pin "1") (pinfunction "1_1") (pintype "passive"))
      (node (ref "C28") (pin "2") (pinfunction "2_2") (pintype "passive"))
      (node (ref "C30") (pin "2") (pinfunction "2_2") (pintype "passive"))
      (node (ref "C32") (pin "2") (pinfunction "2_2") (pintype "passive"))
      (node (ref "IC1") (pin "5") (pinfunction "V+_5") (pintype "bidirectional"))
      (node (ref "IC2") (pin "16") (pinfunction "VCCB_16") (pintype "bidirectional"))
      (node (ref "IC4") (pin "3") (pinfunction "INPUT_3") (pintype "bidirectional"))
      (node (ref "IC6") (pin "16") (pinfunction "VCCB_16") (pintype "bidirectional"))
      (node (ref "IC7") (pin "16") (pinfunction "VCCB_16") (pintype "bidirectional"))
      (node (ref "POWER1") (pin "2") (pinfunction "2_2") (pintype "passive"))
      (node (ref "POWER1") (pin "5") (pinfunction "5_5") (pintype "passive"))
      (node (ref "Q3") (pin "2") (pinfunction "S_2") (pintype "bidirectional"))
      (node (ref "U$8") (pin "P$1") (pinfunction "MP_P$1") (pintype "passive"))
    )
    (net (code "18") (name "12V") (class "Default")
      (node (ref "12V") (pin "A") (pinfunction "A_A") (pintype "passive"))
      (node (ref "POWER1") (pin "8") (pinfunction "8_8") (pintype "passive"))
      (node (ref "R8") (pin "2") (pinfunction "2_2") (pintype "passive"))
      (node (ref "U$9") (pin "P$1") (pinfunction "MP_P$1") (pintype "passive"))
    )
    (net (code "19") (name "A0{slash}ADC1_6{slash}GPIO34") (class "Default")
      (node (ref "IC7") (pin "10") (pinfunction "A8_10") (pintype "bidirectional"))
      (node (ref "IC9") (pin "6") (pinfunction "IO34_6") (pintype "bidirectional"))
    )
    (net (code "20") (name "A0{slash}ADC1_6{slash}GPIO34_5V") (class "Default")
      (node (ref "IC7") (pin "11") (pinfunction "B8_11") (pintype "bidirectional"))
      (node (ref "JANALOG1") (pin "1") (pinfunction "1_1") (pintype "passive"))
    )
    (net (code "21") (name "A1{slash}ADC1_7{slash}GPIO35") (class "Default")
      (node (ref "IC7") (pin "9") (pinfunction "A7_9") (pintype "bidirectional"))
      (node (ref "IC9") (pin "7") (pinfunction "IO35_7") (pintype "bidirectional"))
    )
    (net (code "22") (name "A1{slash}ADC1_7{slash}GPIO35_5V") (class "Default")
      (node (ref "IC7") (pin "12") (pinfunction "B7_12") (pintype "bidirectional"))
      (node (ref "JANALOG1") (pin "2") (pinfunction "2_2") (pintype "passive"))
    )
    (net (code "23") (name "A2{slash}ADC1_4{slash}GPIO32") (class "Default")
      (node (ref "IC7") (pin "8") (pinfunction "A6_8") (pintype "bidirectional"))
      (node (ref "IC9") (pin "8") (pinfunction "IO32_8") (pintype "bidirectional"))
    )
    (net (code "24") (name "A2{slash}ADC1_4{slash}GPIO32_5V") (class "Default")
      (node (ref "IC7") (pin "13") (pinfunction "B6_13") (pintype "bidirectional"))
      (node (ref "JANALOG1") (pin "3") (pinfunction "3_3") (pintype "passive"))
    )
    (net (code "25") (name "A3{slash}ADC1_5{slash}GPIO33") (class "Default")
      (node (ref "IC7") (pin "7") (pinfunction "A5_7") (pintype "bidirectional"))
      (node (ref "IC9") (pin "9") (pinfunction "IO33_9") (pintype "bidirectional"))
    )
    (net (code "26") (name "A3{slash}ADC1_5{slash}GPIO33_5V") (class "Default")
      (node (ref "IC7") (pin "14") (pinfunction "B5_14") (pintype "bidirectional"))
      (node (ref "JANALOG1") (pin "4") (pinfunction "4_4") (pintype "passive"))
    )
    (net (code "27") (name "A4{slash}TXCAN{slash}ADC2_0{slash}GPIO4") (class "Default")
      (node (ref "CAN_TX") (pin "1") (pinfunction "1_1") (pintype "passive"))
      (node (ref "IC7") (pin "4") (pinfunction "A4_4") (pintype "bidirectional"))
      (node (ref "IC9") (pin "26") (pinfunction "IO4_26") (pintype "bidirectional"))
    )
    (net (code "28") (name "A4{slash}TXCAN{slash}ADC2_0{slash}GPIO4_5V") (class "Default")
      (node (ref "IC7") (pin "17") (pinfunction "B4_17") (pintype "bidirectional"))
      (node (ref "JANALOG1") (pin "5") (pinfunction "5_5") (pintype "passive"))
    )
    (net (code "29") (name "A5{slash}ADC2_2{slash}SD_DAT0{slash}GPIO2") (class "Default")
      (node (ref "D6") (pin "1") (pinfunction "A1_1") (pintype "bidirectional"))
      (node (ref "IC7") (pin "3") (pinfunction "A3_3") (pintype "bidirectional"))
      (node (ref "IC9") (pin "24") (pinfunction "IO2_24") (pintype "bidirectional"))
      (node (ref "J-SD_DAT") (pin "1") (pinfunction "1_1") (pintype "passive"))
    )
    (net (code "30") (name "A5{slash}ADC2_2{slash}SD_DATO{slash}GPIO2_5V") (class "Default")
      (node (ref "IC7") (pin "18") (pinfunction "B3_18") (pintype "bidirectional"))
      (node (ref "JANALOG1") (pin "6") (pinfunction "6_6") (pintype "passive"))
    )
    (net (code "31") (name "AREF{slash}GPI39") (class "Default")
      (node (ref "IC9") (pin "5") (pinfunction "SENSOR_VN_5") (pintype "bidirectional"))
      (node (ref "JHIGH1") (pin "8") (pinfunction "8_8") (pintype "passive"))
    )
    (net (code "32") (name "CANH_P") (class "Default")
      (node (ref "C109") (pin "2") (pinfunction "2_2") (pintype "passive"))
      (node (ref "D101") (pin "2") (pinfunction "A_2_2") (pintype "bidirectional"))
      (node (ref "J5") (pin "4") (pinfunction "4_4") (pintype "passive"))
      (node (ref "J6") (pin "4") (pinfunction "4_4") (pintype "passive"))
      (node (ref "R108") (pin "1") (pinfunction "1_1") (pintype "passive"))
      (node (ref "U3") (pin "7") (pinfunction "CANH_7") (pintype "bidirectional"))
    )
    (net (code "33") (name "CANL_N") (class "Default")
      (node (ref "C108") (pin "2") (pinfunction "2_2") (pintype "passive"))
      (node (ref "D101") (pin "1") (pinfunction "A_1_1") (pintype "bidirectional"))
      (node (ref "J5") (pin "3") (pinfunction "3_3") (pintype "passive"))
      (node (ref "J6") (pin "3") (pinfunction "3_3") (pintype "passive"))
      (node (ref "R107") (pin "2") (pinfunction "2_2") (pintype "passive"))
      (node (ref "U3") (pin "6") (pinfunction "CANL_6") (pintype "bidirectional"))
    )
    (net (code "34") (name "CC2") (class "Default")
      (node (ref "J4") (pin "B5") (pinfunction "CC2_B5") (pintype "bidirectional"))
      (node (ref "R2") (pin "2") (pinfunction "2_2") (pintype "passive"))
    )
    (net (code "35") (name "CS{slash}D10{slash}GPIO5") (class "Default")
      (node (ref "IC6") (pin "8") (pinfunction "A6_8") (pintype "bidirectional"))
      (node (ref "IC9") (pin "29") (pinfunction "IO5_29") (pintype "bidirectional"))
    )
    (net (code "36") (name "CS{slash}D10{slash}GPIO5_5V") (class "Default")
      (node (ref "IC6") (pin "13") (pinfunction "B6_13") (pintype "bidirectional"))
      (node (ref "JHIGH1") (pin "3") (pinfunction "3_3") (pintype "passive"))
    )
    (net (code "37") (name "D0{slash}UART_RXD") (class "Default")
      (node (ref "IC10") (pin "25") (pinfunction "RXD_25") (pintype "bidirectional"))
      (node (ref "IC2") (pin "10") (pinfunction "A8_10") (pintype "bidirectional"))
      (node (ref "IC9") (pin "34") (pinfunction "RXD0_34") (pintype "bidirectional"))
    )
    (net (code "38") (name "D0{slash}UART_RXD_5V") (class "Default")
      (node (ref "IC2") (pin "11") (pinfunction "B8_11") (pintype "bidirectional"))
      (node (ref "JLOW1") (pin "1") (pinfunction "1_1") (pintype "passive"))
    )
    (net (code "39") (name "D1{slash}UART_TXD") (class "Default")
      (node (ref "IC10") (pin "26") (pinfunction "TXD_26") (pintype "bidirectional"))
      (node (ref "IC2") (pin "9") (pinfunction "A7_9") (pintype "bidirectional"))
      (node (ref "IC9") (pin "35") (pinfunction "TXD0_35") (pintype "bidirectional"))
    )
    (net (code "40") (name "D1{slash}UART_TXD_5V") (class "Default")
      (node (ref "IC2") (pin "12") (pinfunction "B7_12") (pintype "bidirectional"))
      (node (ref "JLOW1") (pin "2") (pinfunction "2_2") (pintype "passive"))
    )
    (net (code "41") (name "D2{slash}EMAC_RXD1{slash}GPIO26") (class "Default")
      (node (ref "IC11") (pin "3") (pinfunction "A1_3") (pintype "bidirectional"))
      (node (ref "IC9") (pin "11") (pinfunction "IO26_11") (pintype "bidirectional"))
    )
    (net (code "42") (name "D2{slash}GPIO26") (class "Default")
      (node (ref "IC11") (pin "35") (pinfunction "C1_35") (pintype "bidirectional"))
      (node (ref "IC2") (pin "8") (pinfunction "A6_8") (pintype "bidirectional"))
    )
    (net (code "43") (name "D2{slash}GPIO26_5V") (class "Default")
      (node (ref "IC2") (pin "13") (pinfunction "B6_13") (pintype "bidirectional"))
      (node (ref "JLOW1") (pin "3") (pinfunction "3_3") (pintype "passive"))
    )
    (net (code "44") (name "D3{slash}EMAC_RXD0{slash}GPIO25") (class "Default")
      (node (ref "IC11") (pin "6") (pinfunction "A2_6") (pintype "bidirectional"))
      (node (ref "IC9") (pin "10") (pinfunction "IO25_10") (pintype "bidirectional"))
    )
    (net (code "45") (name "D3{slash}GPIO25") (class "Default")
      (node (ref "IC11") (pin "32") (pinfunction "C2_32") (pintype "bidirectional"))
      (node (ref "IC2") (pin "7") (pinfunction "A5_7") (pintype "bidirectional"))
    )
    (net (code "46") (name "D3{slash}GPIO25_5V") (class "Default")
      (node (ref "IC2") (pin "14") (pinfunction "B5_14") (pintype "bidirectional"))
      (node (ref "JLOW1") (pin "4") (pinfunction "4_4") (pintype "passive"))
    )
    (net (code "47") (name "D4{slash}EMAC_CO180{slash}GPIO17") (class "Default")
      (node (ref "IC11") (pin "2") (pinfunction "A0_2") (pintype "bidirectional"))
      (node (ref "IC9") (pin "28") (pinfunction "IO17_28") (pintype "bidirectional"))
    )
    (net (code "48") (name "D4{slash}GPIO17") (class "Default")
      (node (ref "IC11") (pin "36") (pinfunction "C0_36") (pintype "bidirectional"))
      (node (ref "IC2") (pin "4") (pinfunction "A4_4") (pintype "bidirectional"))
    )
    (net (code "49") (name "D4{slash}GPIO17_5V") (class "Default")
      (node (ref "IC2") (pin "17") (pinfunction "B4_17") (pintype "bidirectional"))
      (node (ref "JLOW1") (pin "5") (pinfunction "5_5") (pintype "passive"))
    )
    (net (code "50") (name "D5{slash}GPIO16") (class "Default")
      (node (ref "IC2") (pin "3") (pinfunction "A3_3") (pintype "bidirectional"))
      (node (ref "IC9") (pin "27") (pinfunction "IO16_27") (pintype "bidirectional"))
    )
    (net (code "51") (name "D5{slash}GPIO16_5V") (class "Default")
      (node (ref "IC2") (pin "18") (pinfunction "B3_18") (pintype "bidirectional"))
      (node (ref "JLOW1") (pin "6") (pinfunction "6_6") (pintype "passive"))
    )
    (net (code "52") (name "D6{slash}EMAC_RX_CRS_DV{slash}GPIO27") (class "Default")
      (node (ref "IC11") (pin "7") (pinfunction "A3_7") (pintype "bidirectional"))
      (node (ref "IC9") (pin "12") (pinfunction "IO27_12") (pintype "bidirectional"))
    )
    (net (code "53") (name "D6{slash}GPIO27") (class "Default")
      (node (ref "IC11") (pin "31") (pinfunction "C3_31") (pintype "bidirectional"))
      (node (ref "IC2") (pin "2") (pinfunction "A2_2") (pintype "bidirectional"))
    )
    (net (code "54") (name "D6{slash}GPIO27_5V") (class "Default")
      (node (ref "IC2") (pin "19") (pinfunction "B2_19") (pintype "bidirectional"))
      (node (ref "JLOW1") (pin "7") (pinfunction "7_7") (pintype "passive"))
    )
    (net (code "55") (name "D7{slash}SD_CLK{slash}GPIO14") (class "Default")
      (node (ref "IC2") (pin "1") (pinfunction "A1_1") (pintype "bidirectional"))
      (node (ref "IC9") (pin "13") (pinfunction "IO14_13") (pintype "bidirectional"))
      (node (ref "J_SD_CLK") (pin "1") (pinfunction "1_1") (pintype "passive"))
    )
    (net (code "56") (name "D7{slash}SD_CLK{slash}GPIO14_5V") (class "Default")
      (node (ref "IC2") (pin "20") (pinfunction "B1_20") (pintype "bidirectional"))
      (node (ref "JLOW1") (pin "8") (pinfunction "8_8") (pintype "passive"))
    )
    (net (code "57") (name "D8{slash}GPIO12") (class "Default")
      (node (ref "IC6") (pin "10") (pinfunction "A8_10") (pintype "bidirectional"))
      (node (ref "IC9") (pin "14") (pinfunction "IO12_14") (pintype "bidirectional"))
    )
    (net (code "58") (name "D8{slash}GPIO12_5V") (class "Default")
      (node (ref "IC6") (pin "11") (pinfunction "B8_11") (pintype "bidirectional"))
      (node (ref "JHIGH1") (pin "1") (pinfunction "1_1") (pintype "passive"))
    )
    (net (code "59") (name "D9{slash}GPIO13") (class "Default")
      (node (ref "IC6") (pin "9") (pinfunction "A7_9") (pintype "bidirectional"))
      (node (ref "IC9") (pin "16") (pinfunction "IO13_16") (pintype "bidirectional"))
    )
    (net (code "60") (name "D9{slash}GPIO13_5V") (class "Default")
      (node (ref "IC6") (pin "12") (pinfunction "B7_12") (pintype "bidirectional"))
      (node (ref "JHIGH1") (pin "2") (pinfunction "2_2") (pintype "passive"))
    )
    (net (code "61") (name "EMAC_CO180") (class "Default")
      (node (ref "IC11") (pin "38") (pinfunction "B0_38") (pintype "bidirectional"))
      (node (ref "U2") (pin "5") (pinfunction "XTAL1/CLKIN_5") (pintype "bidirectional"))
    )
    (net (code "62") (name "EMAC_MDC") (class "Default")
      (node (ref "IC11") (pin "28") (pinfunction "B5_28") (pintype "bidirectional"))
      (node (ref "U2") (pin "17") (pinfunction "MDC_17") (pintype "bidirectional"))
    )
    (net (code "63") (name "EMAC_MDIO") (class "Default")
      (node (ref "IC11") (pin "29") (pinfunction "B4_29") (pintype "bidirectional"))
      (node (ref "R53") (pin "1") (pinfunction "1_1") (pintype "passive"))
      (node (ref "U2") (pin "16") (pinfunction "MDIO_16") (pintype "bidirectional"))
    )
    (net (code "64") (name "EMAC_RXD0") (class "Default")
      (node (ref "IC11") (pin "34") (pinfunction "B2_34") (pintype "bidirectional"))
      (node (ref "R51") (pin "1") (pinfunction "1_1") (pintype "passive"))
      (node (ref "U2") (pin "11") (pinfunction "RXD0/MODE0_11") (pintype "bidirectional"))
    )
    (net (code "65") (name "EMAC_RXD1") (class "Default")
      (node (ref "IC11") (pin "37") (pinfunction "B1_37") (pintype "bidirectional"))
      (node (ref "R52") (pin "1") (pinfunction "1_1") (pintype "passive"))
      (node (ref "U2") (pin "10") (pinfunction "RXD1/MODE1_10") (pintype "bidirectional"))
    )
    (net (code "66") (name "EMAC_RX_CRS_DV") (class "Default")
      (node (ref "IC11") (pin "33") (pinfunction "B3_33") (pintype "bidirectional"))
      (node (ref "R54") (pin "1") (pinfunction "1_1") (pintype "passive"))
      (node (ref "U2") (pin "15") (pinfunction "COL/CRS_DV/MODE2_15") (pintype "bidirectional"))
    )
    (net (code "67") (name "EMAC_TXD0") (class "Default")
      (node (ref "IC11") (pin "24") (pinfunction "B7_24") (pintype "bidirectional"))
      (node (ref "U2") (pin "22") (pinfunction "TXD0_22") (pintype "input"))
    )
    (net (code "68") (name "EMAC_TXD1") (class "Default")
      (node (ref "IC11") (pin "17") (pinfunction "LED__B0_17") (pintype "bidirectional"))
      (node (ref "U2") (pin "23") (pinfunction "TXD1_23") (pintype "input"))
    )
    (net (code "69") (name "EMAC_TX_EN") (class "Default")
      (node (ref "IC11") (pin "25") (pinfunction "B6_25") (pintype "bidirectional"))
      (node (ref "U2") (pin "21") (pinfunction "TXEN_21") (pintype "input"))
    )
    (net (code "70") (name "ESP_EN") (class "Default")
      (node (ref "C10") (pin "1") (pinfunction "1_1") (pintype "passive"))
      (node (ref "C6") (pin "1") (pinfunction "1_1") (pintype "passive"))
      (node (ref "IC9") (pin "3") (pinfunction "EN_3") (pintype "bidirectional"))
      (node (ref "POWER1") (pin "3") (pinfunction "3_3") (pintype "passive"))
      (node (ref "Q1") (pin "3") (pinfunction "C_3") (pintype "bidirectional"))
      (node (ref "R111") (pin "1") (pinfunction "1_1") (pintype "passive"))
      (node (ref "S3") (pin "A1") (pinfunction "NO_1_A1") (pintype "bidirectional"))
      (node (ref "S3") (pin "A2") (pinfunction "NO_2_A2") (pintype "bidirectional"))
    )
    (net (code "71") (name "ETH_LED_G") (class "Default")
      (node (ref "J9") (pin "10") (pinfunction "GC_10") (pintype "passive"))
      (node (ref "R57") (pin "2") (pinfunction "2_2") (pintype "passive"))
    )
    (net (code "72") (name "ETH_LED_Y") (class "Default")
      (node (ref "J9") (pin "12") (pinfunction "YA_12") (pintype "passive"))
      (node (ref "R58") (pin "2") (pinfunction "2_2") (pintype "passive"))
    )
    (net (code "73") (name "ETH_VDDCR") (class "Default")
      (node (ref "C7") (pin "1") (pinfunction "1_1") (pintype "passive"))
      (node (ref "C8") (pin "1") (pinfunction "1_1") (pintype "passive"))
      (node (ref "U2") (pin "6") (pinfunction "VDDCR_6") (pintype "power_in"))
    )
    (net (code "74") (name "GND") (class "Default")
      (node (ref "C1") (pin "2") (pinfunction "2_2") (pintype "passive"))
      (node (ref "C10") (pin "2") (pinfunction "2_2") (pintype "passive"))
      (node (ref "C103") (pin "2") (pinfunction "2_2") (pintype "passive"))
      (node (ref "C107") (pin "1") (pinfunction "1_1") (pintype "passive"))
      (node (ref "C108") (pin "1") (pinfunction "1_1") (pintype "passive"))
      (node (ref "C109") (pin "1") (pinfunction "1_1") (pintype "passive"))
      (node (ref "C19") (pin "2") (pinfunction "2_2") (pintype "passive"))
      (node (ref "C2") (pin "2") (pinfunction "2_2") (pintype "passive"))
      (node (ref "C20") (pin "2") (pinfunction "2_2") (pintype "passive"))
      (node (ref "C21") (pin "2") (pinfunction "2_2") (pintype "passive"))
      (node (ref "C22") (pin "2") (pinfunction "2_2") (pintype "passive"))
      (node (ref "C23") (pin "2") (pinfunction "2_2") (pintype "passive"))
      (node (ref "C24") (pin "2") (pinfunction "2_2") (pintype "passive"))
      (node (ref "C27") (pin "1") (pinfunction "1_1") (pintype "passive"))
      (node (ref "C28") (pin "1") (pinfunction "1_1") (pintype "passive"))
      (node (ref "C29") (pin "1") (pinfunction "1_1") (pintype "passive"))
      (node (ref "C3") (pin "2") (pinfunction "2_2") (pintype "passive"))
      (node (ref "C30") (pin "1") (pinfunction "1_1") (pintype "passive"))
      (node (ref "C31") (pin "1") (pinfunction "1_1") (pintype "passive"))
      (node (ref "C32") (pin "1") (pinfunction "1_1") (pintype "passive"))
      (node (ref "C33") (pin "2") (pinfunction "2_2") (pintype "passive"))
      (node (ref "C34") (pin "2") (pinfunction "2_2") (pintype "passive"))
      (node (ref "C35") (pin "1") (pinfunction "1_1") (pintype "passive"))
      (node (ref "C4") (pin "2") (pinfunction "2_2") (pintype "passive"))
      (node (ref "C43") (pin "2") (pinfunction "2_2") (pintype "passive"))
      (node (ref "C5") (pin "1") (pinfunction "1_1") (pintype "passive"))
      (node (ref "C6") (pin "2") (pinfunction "2_2") (pintype "passive"))
      (node (ref "C7") (pin "2") (pinfunction "2_2") (pintype "passive"))
      (node (ref "C8") (pin "2") (pinfunction "2_2") (pintype "passive"))
      (node (ref "C9") (pin "2") (pinfunction "2_2") (pintype "passive"))
      (node (ref "D101") (pin "3") (pinfunction "A_3_3") (pintype "bidirectional"))
      (node (ref "D7") (pin "2") (pinfunction "GND_2") (pintype "bidirectional"))
      (node (ref "IC1") (pin "2") (pinfunction "V-_2") (pintype "bidirectional"))
      (node (ref "IC10") (pin "29") (pinfunction "GND_2_29") (pintype "bidirectional"))
      (node (ref "IC10") (pin "3") (pinfunction "GND_1_3") (pintype "bidirectional"))
      (node (ref "IC11") (pin "43") (pinfunction "GND_43") (pintype "bidirectional"))
      (node (ref "IC11") (pin "5") (pinfunction "PD_5") (pintype "bidirectional"))
      (node (ref "IC2") (pin "15") (pinfunction "GND_15") (pintype "bidirectional"))
      (node (ref "IC3") (pin "2") (pinfunction "GND_2") (pintype "bidirectional"))
      (node (ref "IC4") (pin "1") (pinfunction "GND_1") (pintype "bidirectional"))
      (node (ref "IC6") (pin "15") (pinfunction "GND_15") (pintype "bidirectional"))
      (node (ref "IC7") (pin "15") (pinfunction "GND_15") (pintype "bidirectional"))
      (node (ref "IC9") (pin "1") (pinfunction "GND_1_1") (pintype "bidirectional"))
      (node (ref "IC9") (pin "15") (pinfunction "GND_2_15") (pintype "bidirectional"))
      (node (ref "IC9") (pin "38") (pinfunction "GND_3_38") (pintype "bidirectional"))
      (node (ref "IC9") (pin "39") (pinfunction "GND_4_39") (pintype "bidirectional"))
      (node (ref "IC9") (pin "40") (pinfunction "GND_5_40") (pintype "bidirectional"))
      (node (ref "IC9") (pin "41") (pinfunction "GND_6_41") (pintype "bidirectional"))
      (node (ref "IC9") (pin "42") (pinfunction "GND_7_42") (pintype "bidirectional"))
      (node (ref "IC9") (pin "43") (pinfunction "GND_8_43") (pintype "bidirectional"))
      (node (ref "IC9") (pin "44") (pinfunction "GND_9_44") (pintype "bidirectional"))
      (node (ref "IC9") (pin "45") (pinfunction "GND_10_45") (pintype "bidirectional"))
      (node (ref "IC9") (pin "46") (pinfunction "GND_11_46") (pintype "bidirectional"))
      (node (ref "IC9") (pin "47") (pinfunction "GND_12_47") (pintype "bidirectional"))
      (node (ref "J4") (pin "A1_B12") (pinfunction "GND_A1_B12") (pintype "power_in"))
      (node (ref "J4") (pin "B1_A12") (pinfunction "GND_B1_A12") (pintype "power_in"))
      (node (ref "J5") (pin "1") (pinfunction "1_1") (pintype "passive"))
      (node (ref "J6") (pin "1") (pinfunction "1_1") (pintype "passive"))
      (node (ref "J9") (pin "11") (pinfunction "YC_11") (pintype "passive"))
      (node (ref "J9") (pin "8") (pinfunction "GND_8") (pintype "power_in"))
      (node (ref "JHIGH1") (pin "7") (pinfunction "7_7") (pintype "passive"))
      (node (ref "MICRO_SD1") (pin "6") (pinfunction "VSS_6") (pintype "power_in"))
      (node (ref "MICRO_SD1") (pin "MP1") (pinfunction "SHIELD_MP1") (pintype "power_in"))
      (node (ref "MICRO_SD1") (pin "MP2") (pinfunction "SHIELD_MP2") (pintype "power_in"))
      (node (ref "MICRO_SD1") (pin "MP3") (pinfunction "SHIELD_MP3") (pintype "power_in"))
      (node (ref "MICRO_SD1") (pin "MP4") (pinfunction "SHIELD_MP4") (pintype "power_in"))
      (node (ref "POWER1") (pin "6") (pinfunction "6_6") (pintype "passive"))
      (node (ref "POWER1") (pin "7") (pinfunction "7_7") (pintype "passive"))
      (node (ref "R1") (pin "1") (pinfunction "1_1") (pintype "passive"))
      (node (ref "R104") (pin "1") (pinfunction "1_1") (pintype "passive"))
      (node (ref "R11") (pin "1") (pinfunction "1_1") (pintype "passive"))
      (node (ref "R12") (pin "1") (pinfunction "1_1") (pintype "passive"))
      (node (ref "R14") (pin "1") (pinfunction "1_1") (pintype "passive"))
      (node (ref "R2") (pin "1") (pinfunction "1_1") (pintype "passive"))
      (node (ref "R29") (pin "1") (pinfunction "1_1") (pintype "passive"))
      (node (ref "R3") (pin "1") (pinfunction "1_1") (pintype "passive"))
      (node (ref "R30") (pin "1") (pinfunction "1_1") (pintype "passive"))
      (node (ref "R31") (pin "1") (pinfunction "1_1") (pintype "passive"))
      (node (ref "R32") (pin "2") (pinfunction "2_2") (pintype "passive"))
      (node (ref "R35") (pin "1") (pinfunction "1_1") (pintype "passive"))
      (node (ref "R49") (pin "2") (pinfunction "2_2") (pintype "passive"))
      (node (ref "R5") (pin "1") (pinfunction "1_1") (pintype "passive"))
      (node (ref "R50") (pin "2") (pinfunction "2_2") (pintype "passive"))
      (node (ref "R56") (pin "1") (pinfunction "1_1") (pintype "passive"))
      (node (ref "R6") (pin "1") (pinfunction "1_1") (pintype "passive"))
      (node (ref "R9") (pin "1") (pinfunction "1_1") (pintype "passive"))
      (node (ref "S3") (pin "B1") (pinfunction "COM_1_B1") (pintype "bidirectional"))
      (node (ref "S3") (pin "B2") (pinfunction "COM_2_B2") (pintype "bidirectional"))
      (node (ref "U$11") (pin "P$1") (pinfunction "MP_P$1") (pintype "passive"))
      (node (ref "U$12") (pin "P$1") (pinfunction "MP_P$1") (pintype "passive"))
      (node (ref "U2") (pin "24") (pinfunction "TXD2_24") (pintype "input"))
      (node (ref "U2") (pin "25") (pinfunction "TXD3_25") (pintype "input"))
      (node (ref "U2") (pin "33") (pinfunction "VSS_33") (pintype "power_in"))
      (node (ref "U3") (pin "2") (pinfunction "GND_2") (pintype "power_in"))
      (node (ref "Z1") (pin "2") (pinfunction "A_2") (pintype "bidirectional"))
    )
    (net (code "75") (name "GPIO0") (class "Default")
      (node (ref "D6") (pin "2") (pinfunction "A2_2") (pintype "bidirectional"))
      (node (ref "IC9") (pin "25") (pinfunction "IO0_25") (pintype "bidirectional"))
      (node (ref "Q2") (pin "3") (pinfunction "C_3") (pintype "bidirectional"))
      (node (ref "R17") (pin "2") (pinfunction "2_2") (pintype "passive"))
    )
    (net (code "76") (name "MISO{slash}D12{slash}EMAC_TXD0{slash}GPIO19") (class "Default")
      (node (ref "IC11") (pin "12") (pinfunction "A7_12") (pintype "bidirectional"))
      (node (ref "IC9") (pin "31") (pinfunction "IO19_31") (pintype "bidirectional"))
    )
    (net (code "77") (name "MISO{slash}D12{slash}GPIO19") (class "Default")
      (node (ref "IC11") (pin "22") (pinfunction "C7_22") (pintype "bidirectional"))
      (node (ref "IC6") (pin "4") (pinfunction "A4_4") (pintype "bidirectional"))
    )
    (net (code "78") (name "MISO{slash}D12{slash}GPIO19_5V") (class "Default")
      (node (ref "IC6") (pin "17") (pinfunction "B4_17") (pintype "bidirectional"))
      (node (ref "JHIGH1") (pin "5") (pinfunction "5_5") (pintype "passive"))
    )
    (net (code "79") (name "MOSI{slash}D11{slash}EMAC_MDC{slash}GPIO23") (class "Default")
      (node (ref "IC11") (pin "10") (pinfunction "A5_10") (pintype "bidirectional"))
      (node (ref "IC9") (pin "37") (pinfunction "IO23_37") (pintype "bidirectional"))
    )
    (net (code "80") (name "MOSI{slash}D11{slash}GPIO23") (class "Default")
      (node (ref "IC11") (pin "26") (pinfunction "C5_26") (pintype "bidirectional"))
      (node (ref "IC6") (pin "7") (pinfunction "A5_7") (pintype "bidirectional"))
    )
    (net (code "81") (name "MOSI{slash}D11{slash}GPIO23_5V") (class "Default")
      (node (ref "IC6") (pin "14") (pinfunction "B5_14") (pintype "bidirectional"))
      (node (ref "JHIGH1") (pin "4") (pinfunction "4_4") (pintype "passive"))
    )
    (net (code "82") (name "Net-(3.3V-PadC)") (class "Default")
      (node (ref "3.3V") (pin "C") (pinfunction "C_C") (pintype "passive"))
      (node (ref "R12") (pin "2") (pinfunction "2_2") (pintype "passive"))
    )
    (net (code "83") (name "Net-(5V-PadC)") (class "Default")
      (node (ref "5V") (pin "C") (pinfunction "C_C") (pintype "passive"))
      (node (ref "R11") (pin "2") (pinfunction "2_2") (pintype "passive"))
    )
    (net (code "84") (name "Net-(12V-PadC)") (class "Default")
      (node (ref "12V") (pin "C") (pinfunction "C_C") (pintype "passive"))
      (node (ref "R9") (pin "2") (pinfunction "2_2") (pintype "passive"))
    )
    (net (code "85") (name "Net-(C21-Pad1)") (class "Default")
      (node (ref "C21") (pin "1") (pinfunction "1_1") (pintype "passive"))
      (node (ref "J9") (pin "15") (pinfunction "SHIELD_15") (pintype "passive"))
      (node (ref "J9") (pin "16") (pinfunction "SHIELD_16") (pintype "passive"))
    )
    (net (code "86") (name "Net-(C107-Pad2)") (class "Default")
      (node (ref "C107") (pin "2") (pinfunction "2_2") (pintype "passive"))
      (node (ref "SJ1") (pin "1") (pinfunction "1_1") (pintype "passive"))
    )
    (net (code "87") (name "Net-(D6-CC)") (class "Default")
      (node (ref "D6") (pin "3") (pinfunction "CC_3") (pintype "bidirectional"))
      (node (ref "R17") (pin "1") (pinfunction "1_1") (pintype "passive"))
    )
    (net (code "88") (name "Net-(F1-Pad1)") (class "Default")
      (node (ref "F1") (pin "1") (pinfunction "1_1") (pintype "bidirectional"))
      (node (ref "J4") (pin "A4_B9") (pinfunction "VBUS_A4_B9") (pintype "power_in"))
      (node (ref "J4") (pin "B4_A9") (pinfunction "VBUS_B4_A9") (pintype "power_in"))
    )
    (net (code "89") (name "Net-(IC1-OUT)") (class "Default")
      (node (ref "IC1") (pin "1") (pinfunction "OUT_1") (pintype "bidirectional"))
      (node (ref "Q3") (pin "1") (pinfunction "G_1") (pintype "bidirectional"))
    )
    (net (code "90") (name "Net-(IC10-RSTB)") (class "Default")
      (node (ref "IC10") (pin "9") (pinfunction "RSTB_9") (pintype "bidirectional"))
      (node (ref "R13") (pin "2") (pinfunction "2_2") (pintype "passive"))
    )
    (net (code "91") (name "Net-(IC10-SUSPENDB)") (class "Default")
      (node (ref "IC10") (pin "11") (pinfunction "SUSPENDB_11") (pintype "bidirectional"))
      (node (ref "R14") (pin "2") (pinfunction "2_2") (pintype "passive"))
    )
    (net (code "92") (name "Net-(J4-CC1)") (class "Default")
      (node (ref "J4") (pin "A5") (pinfunction "CC1_A5") (pintype "bidirectional"))
      (node (ref "R3") (pin "2") (pinfunction "2_2") (pintype "passive"))
    )
    (net (code "93") (name "Net-(J4-SHIELD-PadS1)") (class "Default")
      (node (ref "J4") (pin "S1") (pinfunction "SHIELD_S1") (pintype "passive"))
      (node (ref "J4") (pin "S2") (pinfunction "SHIELD_S2") (pintype "passive"))
      (node (ref "J4") (pin "S3") (pinfunction "SHIELD_S3") (pintype "passive"))
      (node (ref "J4") (pin "S4") (pinfunction "SHIELD_S4") (pintype "passive"))
      (node (ref "R1") (pin "2") (pinfunction "2_2") (pintype "passive"))
    )
    (net (code "94") (name "Net-(Q1-B)") (class "Default")
      (node (ref "Q1") (pin "1") (pinfunction "B_1") (pintype "bidirectional"))
      (node (ref "R16") (pin "1") (pinfunction "1_1") (pintype "passive"))
    )
    (net (code "95") (name "Net-(Q2-B)") (class "Default")
      (node (ref "Q2") (pin "1") (pinfunction "B_1") (pintype "bidirectional"))
      (node (ref "R15") (pin "1") (pinfunction "1_1") (pintype "passive"))
    )
    (net (code "96") (name "Net-(R107-Pad1)") (class "Default")
      (node (ref "R107") (pin "1") (pinfunction "1_1") (pintype "passive"))
      (node (ref "R108") (pin "2") (pinfunction "2_2") (pintype "passive"))
      (node (ref "SJ1") (pin "2") (pinfunction "2_2") (pintype "passive"))
    )
    (net (code "97") (name "Net-(U2-LED1{slash}REGOFF)") (class "Default")
      (node (ref "R58") (pin "1") (pinfunction "1_1") (pintype "passive"))
      (node (ref "U2") (pin "3") (pinfunction "LED1/REGOFF_3") (pintype "bidirectional"))
    )
    (net (code "98") (name "Net-(U2-LED2{slash}NINTSEL)") (class "Default")
      (node (ref "R57") (pin "1") (pinfunction "1_1") (pintype "passive"))
      (node (ref "U2") (pin "2") (pinfunction "LED2/NINTSEL_2") (pintype "bidirectional"))
    )
    (net (code "99") (name "Net-(U2-NRST)") (class "Default")
      (node (ref "C43") (pin "1") (pinfunction "1_1") (pintype "passive"))
      (node (ref "R55") (pin "1") (pinfunction "1_1") (pintype "passive"))
      (node (ref "U2") (pin "19") (pinfunction "NRST_19") (pintype "bidirectional"))
    )
    (net (code "100") (name "Net-(U2-RBIAS)") (class "Default")
      (node (ref "R56") (pin "2") (pinfunction "2_2") (pintype "passive"))
      (node (ref "U2") (pin "32") (pinfunction "RBIAS_32") (pintype "passive"))
    )
    (net (code "101") (name "Net-(U2-RXCLK{slash}PHYAD1)") (class "Default")
      (node (ref "R50") (pin "1") (pinfunction "1_1") (pintype "passive"))
      (node (ref "U2") (pin "7") (pinfunction "RXCLK/PHYAD1_7") (pintype "bidirectional"))
    )
    (net (code "102") (name "Net-(U2-RXD2{slash}RMIISEL)") (class "Default")
      (node (ref "R28") (pin "1") (pinfunction "1_1") (pintype "passive"))
      (node (ref "U2") (pin "9") (pinfunction "RXD2/RMIISEL_9") (pintype "bidirectional"))
    )
    (net (code "103") (name "Net-(U2-RXD3{slash}PHYAD2)") (class "Default")
      (node (ref "R32") (pin "1") (pinfunction "1_1") (pintype "passive"))
      (node (ref "U2") (pin "8") (pinfunction "RXD3/PHYAD2_8") (pintype "bidirectional"))
    )
    (net (code "104") (name "Net-(U2-RXER{slash}RXD4{slash}PHYAD0)") (class "Default")
      (node (ref "R49") (pin "1") (pinfunction "1_1") (pintype "passive"))
      (node (ref "U2") (pin "13") (pinfunction "RXER/RXD4/PHYAD0_13") (pintype "bidirectional"))
    )
    (net (code "105") (name "Net-(U3-RS)") (class "Default")
      (node (ref "R104") (pin "2") (pinfunction "2_2") (pintype "passive"))
      (node (ref "U3") (pin "8") (pinfunction "RS_8") (pintype "input"))
    )
    (net (code "106") (name "OE_A") (class "Default")
      (node (ref "IC2") (pin "6") (pinfunction "OE_6") (pintype "bidirectional"))
      (node (ref "R29") (pin "2") (pinfunction "2_2") (pintype "passive"))
    )
    (net (code "107") (name "OE_B") (class "Default")
      (node (ref "IC6") (pin "6") (pinfunction "OE_6") (pintype "bidirectional"))
      (node (ref "R30") (pin "2") (pinfunction "2_2") (pintype "passive"))
    )
    (net (code "108") (name "OE_C") (class "Default")
      (node (ref "IC7") (pin "6") (pinfunction "OE_6") (pintype "bidirectional"))
      (node (ref "R31") (pin "2") (pinfunction "2_2") (pintype "passive"))
    )
    (net (code "109") (name "PC0") (class "Default")
      (node (ref "IC7") (pin "1") (pinfunction "A1_1") (pintype "bidirectional"))
    )
    (net (code "110") (name "PC0O") (class "Default")
      (node (ref "IC7") (pin "20") (pinfunction "B1_20") (pintype "bidirectional"))
    )
    (net (code "111") (name "PC1") (class "Default")
      (node (ref "IC7") (pin "2") (pinfunction "A2_2") (pintype "bidirectional"))
    )
    (net (code "112") (name "PC1O") (class "Default")
      (node (ref "IC7") (pin "19") (pinfunction "B2_19") (pintype "bidirectional"))
    )
    (net (code "113") (name "RXCAN{slash}GPI36") (class "Default")
      (node (ref "IC9") (pin "4") (pinfunction "SENSOR_VP_4") (pintype "bidirectional"))
      (node (ref "U3") (pin "4") (pinfunction "R_4") (pintype "output"))
    )
    (net (code "114") (name "SCK{slash}D13{slash}EMAC_MDIO{slash}GPIO18") (class "Default")
      (node (ref "IC11") (pin "9") (pinfunction "A4_9") (pintype "bidirectional"))
      (node (ref "IC9") (pin "30") (pinfunction "IO18_30") (pintype "bidirectional"))
    )
    (net (code "115") (name "SCK{slash}D13{slash}GPIO18") (class "Default")
      (node (ref "IC11") (pin "27") (pinfunction "C4_27") (pintype "bidirectional"))
      (node (ref "IC6") (pin "3") (pinfunction "A3_3") (pintype "bidirectional"))
    )
    (net (code "116") (name "SCK{slash}D13{slash}GPIO18_5V") (class "Default")
      (node (ref "IC6") (pin "18") (pinfunction "B3_18") (pintype "bidirectional"))
      (node (ref "JHIGH1") (pin "6") (pinfunction "6_6") (pintype "passive"))
    )
    (net (code "117") (name "SCL{slash}EMAC_TXD1{slash}GPIO22") (class "Default")
      (node (ref "IC11") (pin "15") (pinfunction "LED_A0_15") (pintype "bidirectional"))
      (node (ref "IC9") (pin "36") (pinfunction "IO22_36") (pintype "bidirectional"))
    )
    (net (code "118") (name "SCL{slash}GPIO22") (class "Default")
      (node (ref "IC11") (pin "19") (pinfunction "LED_C0_19") (pintype "bidirectional"))
      (node (ref "IC6") (pin "1") (pinfunction "A1_1") (pintype "bidirectional"))
    )
    (net (code "119") (name "SCL{slash}GPIO22_5V") (class "Default")
      (node (ref "IC6") (pin "20") (pinfunction "B1_20") (pintype "bidirectional"))
      (node (ref "JHIGH1") (pin "10") (pinfunction "10_10") (pintype "passive"))
    )
    (net (code "120") (name "SDA{slash}EMAC_TX_EN{slash}GPIO21") (class "Default")
      (node (ref "IC11") (pin "11") (pinfunction "A6_11") (pintype "bidirectional"))
      (node (ref "IC9") (pin "33") (pinfunction "IO21_33") (pintype "bidirectional"))
    )
    (net (code "121") (name "SDA{slash}GPIO21") (class "Default")
      (node (ref "IC11") (pin "23") (pinfunction "C6_23") (pintype "bidirectional"))
      (node (ref "IC6") (pin "2") (pinfunction "A2_2") (pintype "bidirectional"))
    )
    (net (code "122") (name "SDA{slash}GPIO21_5V") (class "Default")
      (node (ref "IC6") (pin "19") (pinfunction "B2_19") (pintype "bidirectional"))
      (node (ref "JHIGH1") (pin "9") (pinfunction "9_9") (pintype "passive"))
    )
    (net (code "123") (name "SD_CLK{slash}GPIO14_S") (class "Default")
      (node (ref "J_SD_CLK") (pin "2") (pinfunction "2_2") (pintype "passive"))
      (node (ref "R22") (pin "2") (pinfunction "2_2") (pintype "passive"))
    )
    (net (code "124") (name "SD_CMD{slash}GPIO15") (class "Default")
      (node (ref "IC9") (pin "23") (pinfunction "IO15_23") (pintype "bidirectional"))
      (node (ref "J_SD_CMD") (pin "1") (pinfunction "1_1") (pintype "passive"))
    )
    (net (code "125") (name "SD_CMD{slash}GPIO15_S") (class "Default")
      (node (ref "J_SD_CMD") (pin "2") (pinfunction "2_2") (pintype "passive"))
      (node (ref "MICRO_SD1") (pin "3") (pinfunction "CMD_3") (pintype "bidirectional"))
      (node (ref "R23") (pin "1") (pinfunction "1_1") (pintype "passive"))
    )
    (net (code "126") (name "SD_DAT0{slash}GPIO2_S") (class "Default")
      (node (ref "J-SD_DAT") (pin "2") (pinfunction "2_2") (pintype "passive"))
      (node (ref "R18") (pin "1") (pinfunction "1_1") (pintype "passive"))
      (node (ref "R21") (pin "2") (pinfunction "2_2") (pintype "passive"))
    )
    (net (code "127") (name "TXCAN") (class "Default")
      (node (ref "CAN_TX") (pin "2") (pinfunction "2_2") (pintype "passive"))
      (node (ref "U3") (pin "1") (pinfunction "D_1") (pintype "input"))
    )
    (net (code "128") (name "USB_CTS") (class "Default")
      (node (ref "IC10") (pin "23") (pinfunction "CTS_23") (pintype "bidirectional"))
    )
    (net (code "129") (name "USB_DATA_CON_N") (class "Default")
      (node (ref "IC3") (pin "6") (pinfunction "I/O1_2_6") (pintype "bidirectional"))
      (node (ref "J4") (pin "A7") (pinfunction "DN1_A7") (pintype "bidirectional"))
      (node (ref "J4") (pin "B7") (pinfunction "DN2_B7") (pintype "bidirectional"))
    )
    (net (code "130") (name "USB_DATA_CON_P") (class "Default")
      (node (ref "IC3") (pin "4") (pinfunction "I/O2_2_4") (pintype "bidirectional"))
      (node (ref "J4") (pin "A6") (pinfunction "DP1_A6") (pintype "bidirectional"))
      (node (ref "J4") (pin "B6") (pinfunction "DP2_B6") (pintype "bidirectional"))
    )
    (net (code "131") (name "USB_DCD") (class "Default")
      (node (ref "IC10") (pin "1") (pinfunction "DCD_1") (pintype "bidirectional"))
    )
    (net (code "132") (name "USB_DSR") (class "Default")
      (node (ref "IC10") (pin "27") (pinfunction "DSR_27") (pintype "bidirectional"))
    )
    (net (code "133") (name "USB_DTR") (class "Default")
      (node (ref "IC10") (pin "28") (pinfunction "DTR_28") (pintype "bidirectional"))
      (node (ref "Q2") (pin "2") (pinfunction "E_2") (pintype "bidirectional"))
      (node (ref "R16") (pin "2") (pinfunction "2_2") (pintype "passive"))
    )
    (net (code "134") (name "USB_RI") (class "Default")
      (node (ref "IC10") (pin "2") (pinfunction "RI_/_CLK_2") (pintype "bidirectional"))
    )
    (net (code "135") (name "USB_RTS") (class "Default")
      (node (ref "IC10") (pin "24") (pinfunction "RTS_24") (pintype "bidirectional"))
      (node (ref "Q1") (pin "2") (pinfunction "E_2") (pintype "bidirectional"))
      (node (ref "R15") (pin "2") (pinfunction "2_2") (pintype "passive"))
    )
    (net (code "136") (name "VBUS") (class "Default")
      (node (ref "F1") (pin "2") (pinfunction "2_2") (pintype "bidirectional"))
      (node (ref "IC10") (pin "8") (pinfunction "VBUS_8") (pintype "bidirectional"))
      (node (ref "IC3") (pin "5") (pinfunction "VBUS_5") (pintype "bidirectional"))
      (node (ref "Q3") (pin "3") (pinfunction "D_3") (pintype "bidirectional"))
      (node (ref "R10") (pin "1") (pinfunction "1_1") (pintype "passive"))
      (node (ref "R10") (pin "2") (pinfunction "2_2") (pintype "passive"))
      (node (ref "R6") (pin "2") (pinfunction "2_2") (pintype "passive"))
    )
    (net (code "137") (name "VIN") (class "Default")
      (node (ref "J5") (pin "2") (pinfunction "2_2") (pintype "passive"))
      (node (ref "J6") (pin "2") (pinfunction "2_2") (pintype "passive"))
      (node (ref "U$10") (pin "P$1") (pinfunction "MP_P$1") (pintype "passive"))
    )
    (net (code "138") (name "unconnected-(IC9-NC_1-Pad17)") (class "Default")
      (node (ref "IC9") (pin "17") (pinfunction "NC_1_17") (pintype "bidirectional"))
    )
    (net (code "139") (name "unconnected-(IC9-NC_2-Pad18)") (class "Default")
      (node (ref "IC9") (pin "18") (pinfunction "NC_2_18") (pintype "bidirectional"))
    )
    (net (code "140") (name "unconnected-(IC9-NC_3-Pad19)") (class "Default")
      (node (ref "IC9") (pin "19") (pinfunction "NC_3_19") (pintype "bidirectional"))
    )
    (net (code "141") (name "unconnected-(IC9-NC_4-Pad20)") (class "Default")
      (node (ref "IC9") (pin "20") (pinfunction "NC_4_20") (pintype "bidirectional"))
    )
    (net (code "142") (name "unconnected-(IC9-NC_5-Pad21)") (class "Default")
      (node (ref "IC9") (pin "21") (pinfunction "NC_5_21") (pintype "bidirectional"))
    )
    (net (code "143") (name "unconnected-(IC9-NC_6-Pad22)") (class "Default")
      (node (ref "IC9") (pin "22") (pinfunction "NC_6_22") (pintype "bidirectional"))
    )
    (net (code "144") (name "unconnected-(IC9-NC_7-Pad32)") (class "Default")
      (node (ref "IC9") (pin "32") (pinfunction "NC_7_32") (pintype "bidirectional"))
    )
    (net (code "145") (name "unconnected-(IC10-CHR0-Pad15)") (class "Default")
      (node (ref "IC10") (pin "15") (pinfunction "CHR0_15") (pintype "bidirectional"))
    )
    (net (code "146") (name "unconnected-(IC10-CHR1-Pad14)") (class "Default")
      (node (ref "IC10") (pin "14") (pinfunction "CHR1_14") (pintype "bidirectional"))
    )
    (net (code "147") (name "unconnected-(IC10-CHREN-Pad13)") (class "Default")
      (node (ref "IC10") (pin "13") (pinfunction "CHREN_13") (pintype "bidirectional"))
    )
    (net (code "148") (name "unconnected-(IC10-GPIO.0_{slash}_TXT-Pad19)") (class "Default")
      (node (ref "IC10") (pin "19") (pinfunction "GPIO.0_/_TXT_19") (pintype "bidirectional"))
    )
    (net (code "149") (name "unconnected-(IC10-GPIO.1_{slash}_RXT-Pad18)") (class "Default")
      (node (ref "IC10") (pin "18") (pinfunction "GPIO.1_/_RXT_18") (pintype "bidirectional"))
    )
    (net (code "150") (name "unconnected-(IC10-GPIO.2_{slash}_RS485-Pad17)") (class "Default")
      (node (ref "IC10") (pin "17") (pinfunction "GPIO.2_/_RS485_17") (pintype "bidirectional"))
    )
    (net (code "151") (name "unconnected-(IC10-GPIO.3_{slash}_WAKEUP-Pad16)") (class "Default")
      (node (ref "IC10") (pin "16") (pinfunction "GPIO.3_/_WAKEUP_16") (pintype "bidirectional"))
    )
    (net (code "152") (name "unconnected-(IC10-GPIO.4-Pad22)") (class "Default")
      (node (ref "IC10") (pin "22") (pinfunction "GPIO.4_22") (pintype "bidirectional"))
    )
    (net (code "153") (name "unconnected-(IC10-GPIO.5-Pad21)") (class "Default")
      (node (ref "IC10") (pin "21") (pinfunction "GPIO.5_21") (pintype "bidirectional"))
    )
    (net (code "154") (name "unconnected-(IC10-GPIO.6-Pad20)") (class "Default")
      (node (ref "IC10") (pin "20") (pinfunction "GPIO.6_20") (pintype "bidirectional"))
    )
    (net (code "155") (name "unconnected-(IC10-NC-Pad10)") (class "Default")
      (node (ref "IC10") (pin "10") (pinfunction "NC_10") (pintype "no_connect"))
    )
    (net (code "156") (name "unconnected-(IC10-SUSPEND-Pad12)") (class "Default")
      (node (ref "IC10") (pin "12") (pinfunction "SUSPEND_12") (pintype "bidirectional"))
    )
    (net (code "157") (name "unconnected-(IC11-LED_A2-Pad42)") (class "Default")
      (node (ref "IC11") (pin "42") (pinfunction "LED_A2_42") (pintype "bidirectional"))
    )
    (net (code "158") (name "unconnected-(IC11-LED_B1-Pad18)") (class "Default")
      (node (ref "IC11") (pin "18") (pinfunction "LED_B1_18") (pintype "bidirectional"))
    )
    (net (code "159") (name "unconnected-(IC11-LED_C1-Pad20)") (class "Default")
      (node (ref "IC11") (pin "20") (pinfunction "LED_C1_20") (pintype "bidirectional"))
    )
    (net (code "160") (name "unconnected-(IC11-LED__A1-Pad16)") (class "Default")
      (node (ref "IC11") (pin "16") (pinfunction "LED__A1_16") (pintype "bidirectional"))
    )
    (net (code "161") (name "unconnected-(IC11-LED__B2-Pad41)") (class "Default")
      (node (ref "IC11") (pin "41") (pinfunction "LED__B2_41") (pintype "bidirectional"))
    )
    (net (code "162") (name "unconnected-(IC11-LED__C2-Pad40)") (class "Default")
      (node (ref "IC11") (pin "40") (pinfunction "LED__C2_40") (pintype "bidirectional"))
    )
    (net (code "163") (name "unconnected-(IC11-VDD_1-Pad1)") (class "Default")
      (node (ref "IC11") (pin "1") (pinfunction "VDD_1_1") (pintype "bidirectional"))
    )
    (net (code "164") (name "unconnected-(IC11-VDD_2-Pad4)") (class "Default")
      (node (ref "IC11") (pin "4") (pinfunction "VDD_2_4") (pintype "bidirectional"))
    )
    (net (code "165") (name "unconnected-(IC11-VDD_3-Pad8)") (class "Default")
      (node (ref "IC11") (pin "8") (pinfunction "VDD_3_8") (pintype "bidirectional"))
    )
    (net (code "166") (name "unconnected-(IC11-VDD_4-Pad14)") (class "Default")
      (node (ref "IC11") (pin "14") (pinfunction "VDD_4_14") (pintype "bidirectional"))
    )
    (net (code "167") (name "unconnected-(IC11-VDD_5-Pad21)") (class "Default")
      (node (ref "IC11") (pin "21") (pinfunction "VDD_5_21") (pintype "bidirectional"))
    )
    (net (code "168") (name "unconnected-(IC11-VDD_6-Pad30)") (class "Default")
      (node (ref "IC11") (pin "30") (pinfunction "VDD_6_30") (pintype "bidirectional"))
    )
    (net (code "169") (name "unconnected-(J4-SBU1-PadA8)") (class "Default")
      (node (ref "J4") (pin "A8") (pinfunction "SBU1_A8") (pintype "bidirectional"))
    )
    (net (code "170") (name "unconnected-(J4-SBU2-PadB8)") (class "Default")
      (node (ref "J4") (pin "B8") (pinfunction "SBU2_B8") (pintype "bidirectional"))
    )
    (net (code "171") (name "unconnected-(MICRO_SD1-CD-PadCD1)") (class "Default")
      (node (ref "MICRO_SD1") (pin "CD1") (pinfunction "CD_CD1") (pintype "passive"))
    )
    (net (code "172") (name "unconnected-(POWER1-Pad1)") (class "Default")
      (node (ref "POWER1") (pin "1") (pinfunction "1_1") (pintype "passive"))
    )
    (net (code "173") (name "unconnected-(U2-CRS-Pad14)") (class "Default")
      (node (ref "U2") (pin "14") (pinfunction "CRS_14") (pintype "output"))
    )
    (net (code "174") (name "unconnected-(U2-NINT{slash}TXER{slash}TXD4-Pad18)") (class "Default")
      (node (ref "U2") (pin "18") (pinfunction "NINT/TXER/TXD4_18") (pintype "bidirectional"))
    )
    (net (code "175") (name "unconnected-(U2-RXDV-Pad26)") (class "Default")
      (node (ref "U2") (pin "26") (pinfunction "RXDV_26") (pintype "output"))
    )
    (net (code "176") (name "unconnected-(U2-TXCLK-Pad20)") (class "Default")
      (node (ref "U2") (pin "20") (pinfunction "TXCLK_20") (pintype "output"))
    )
    (net (code "177") (name "unconnected-(U2-XTAL2-Pad4)") (class "Default")
      (node (ref "U2") (pin "4") (pinfunction "XTAL2_4") (pintype "bidirectional"))
    )
    (net (code "178") (name "unconnected-(U3-VREF-Pad5)") (class "Default")
      (node (ref "U3") (pin "5") (pinfunction "VREF_5") (pintype "output"))
    )
  )
)
